# ArduinoZero.net
KiCad netlist of a schematic drawn in EAGLE
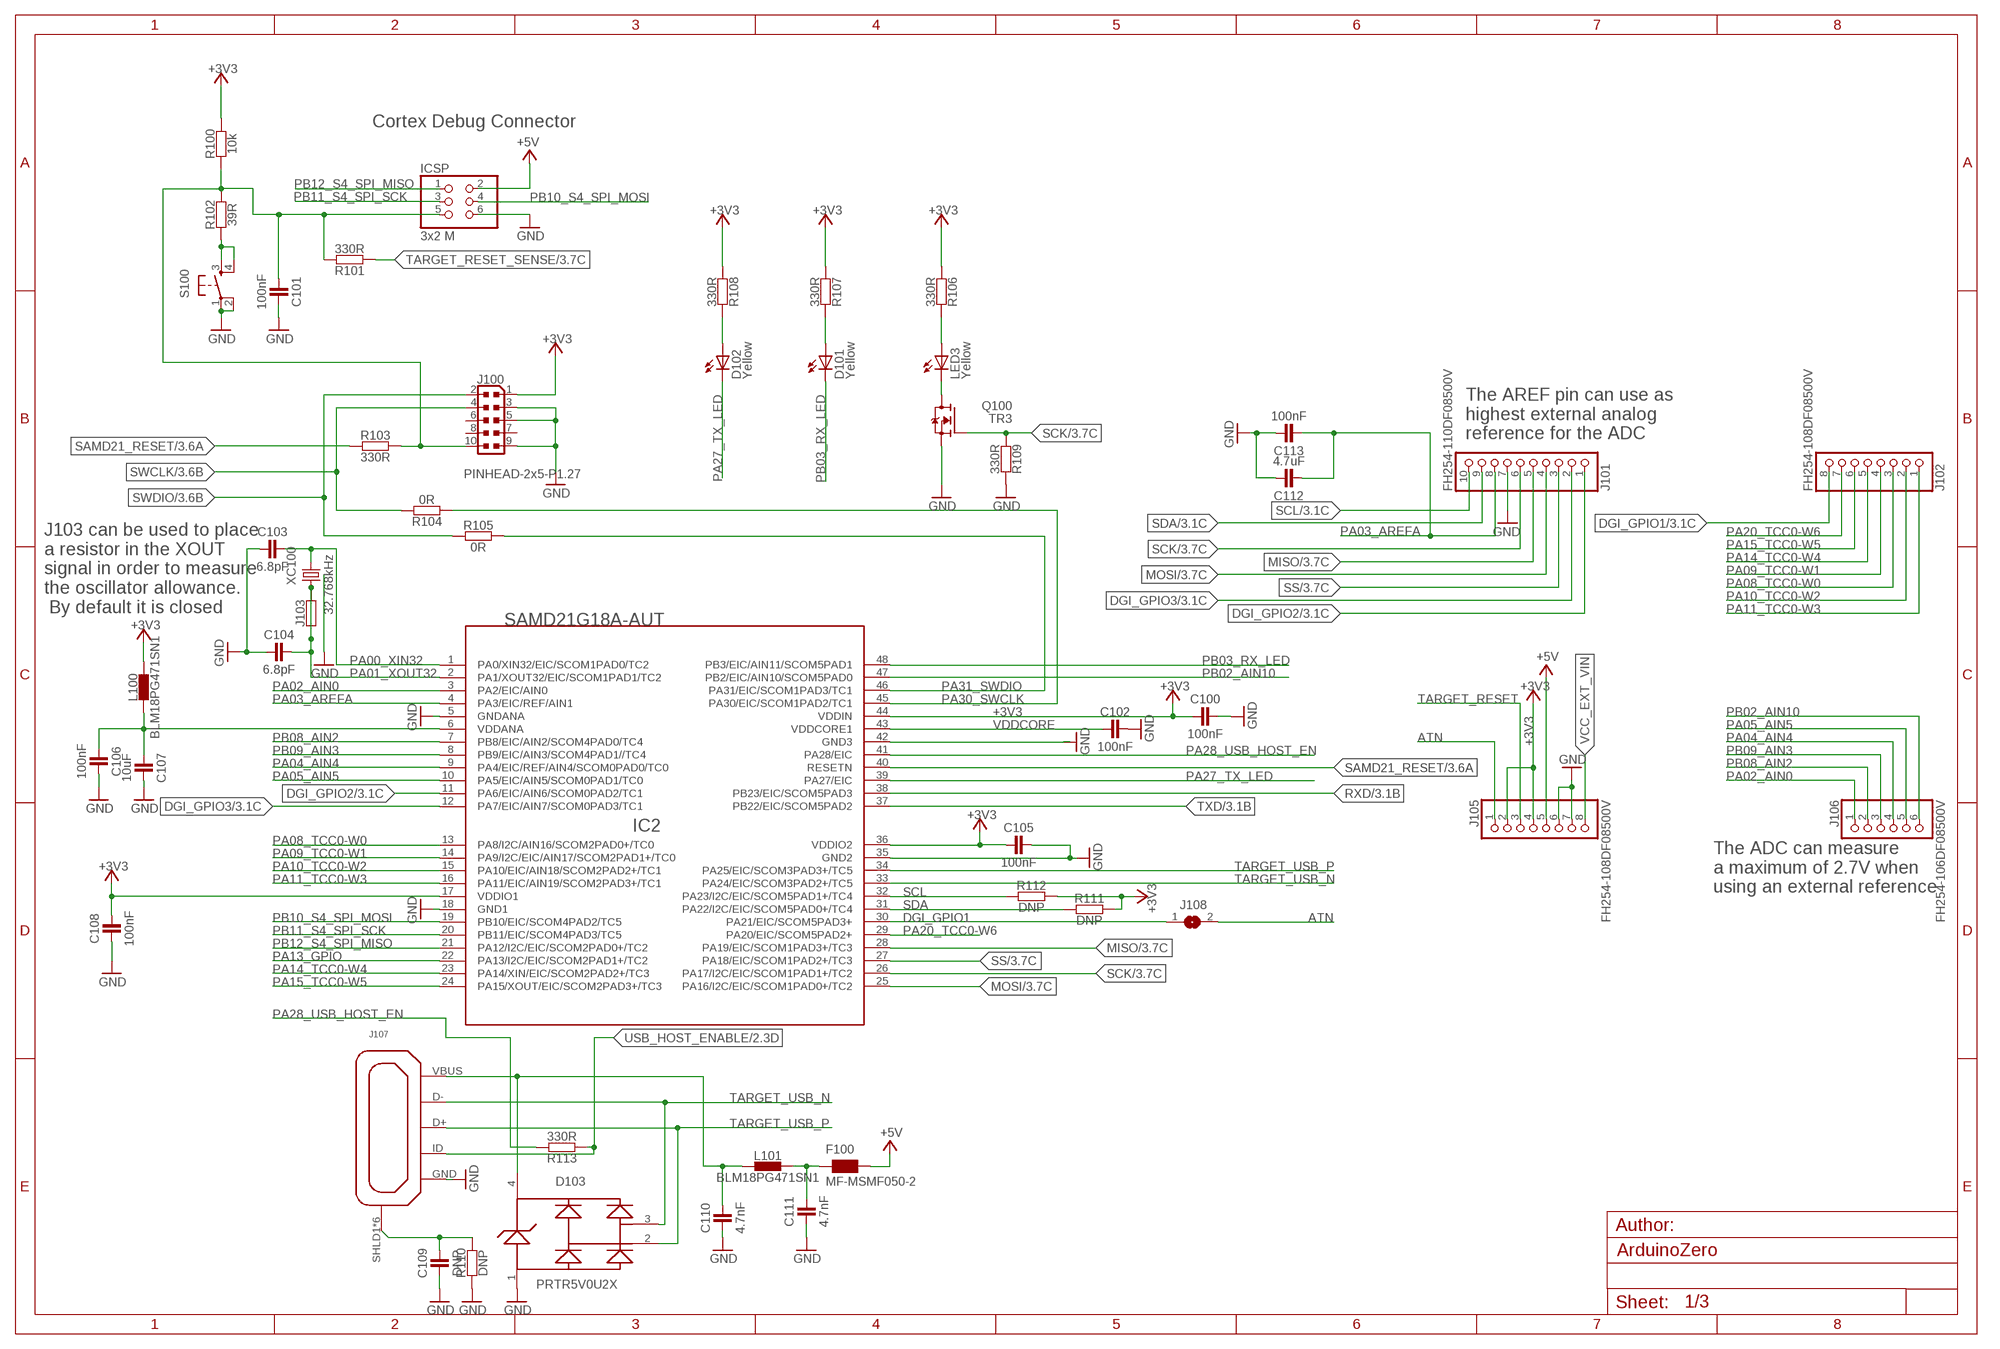
[diagram p0: schematic, sheet 1]
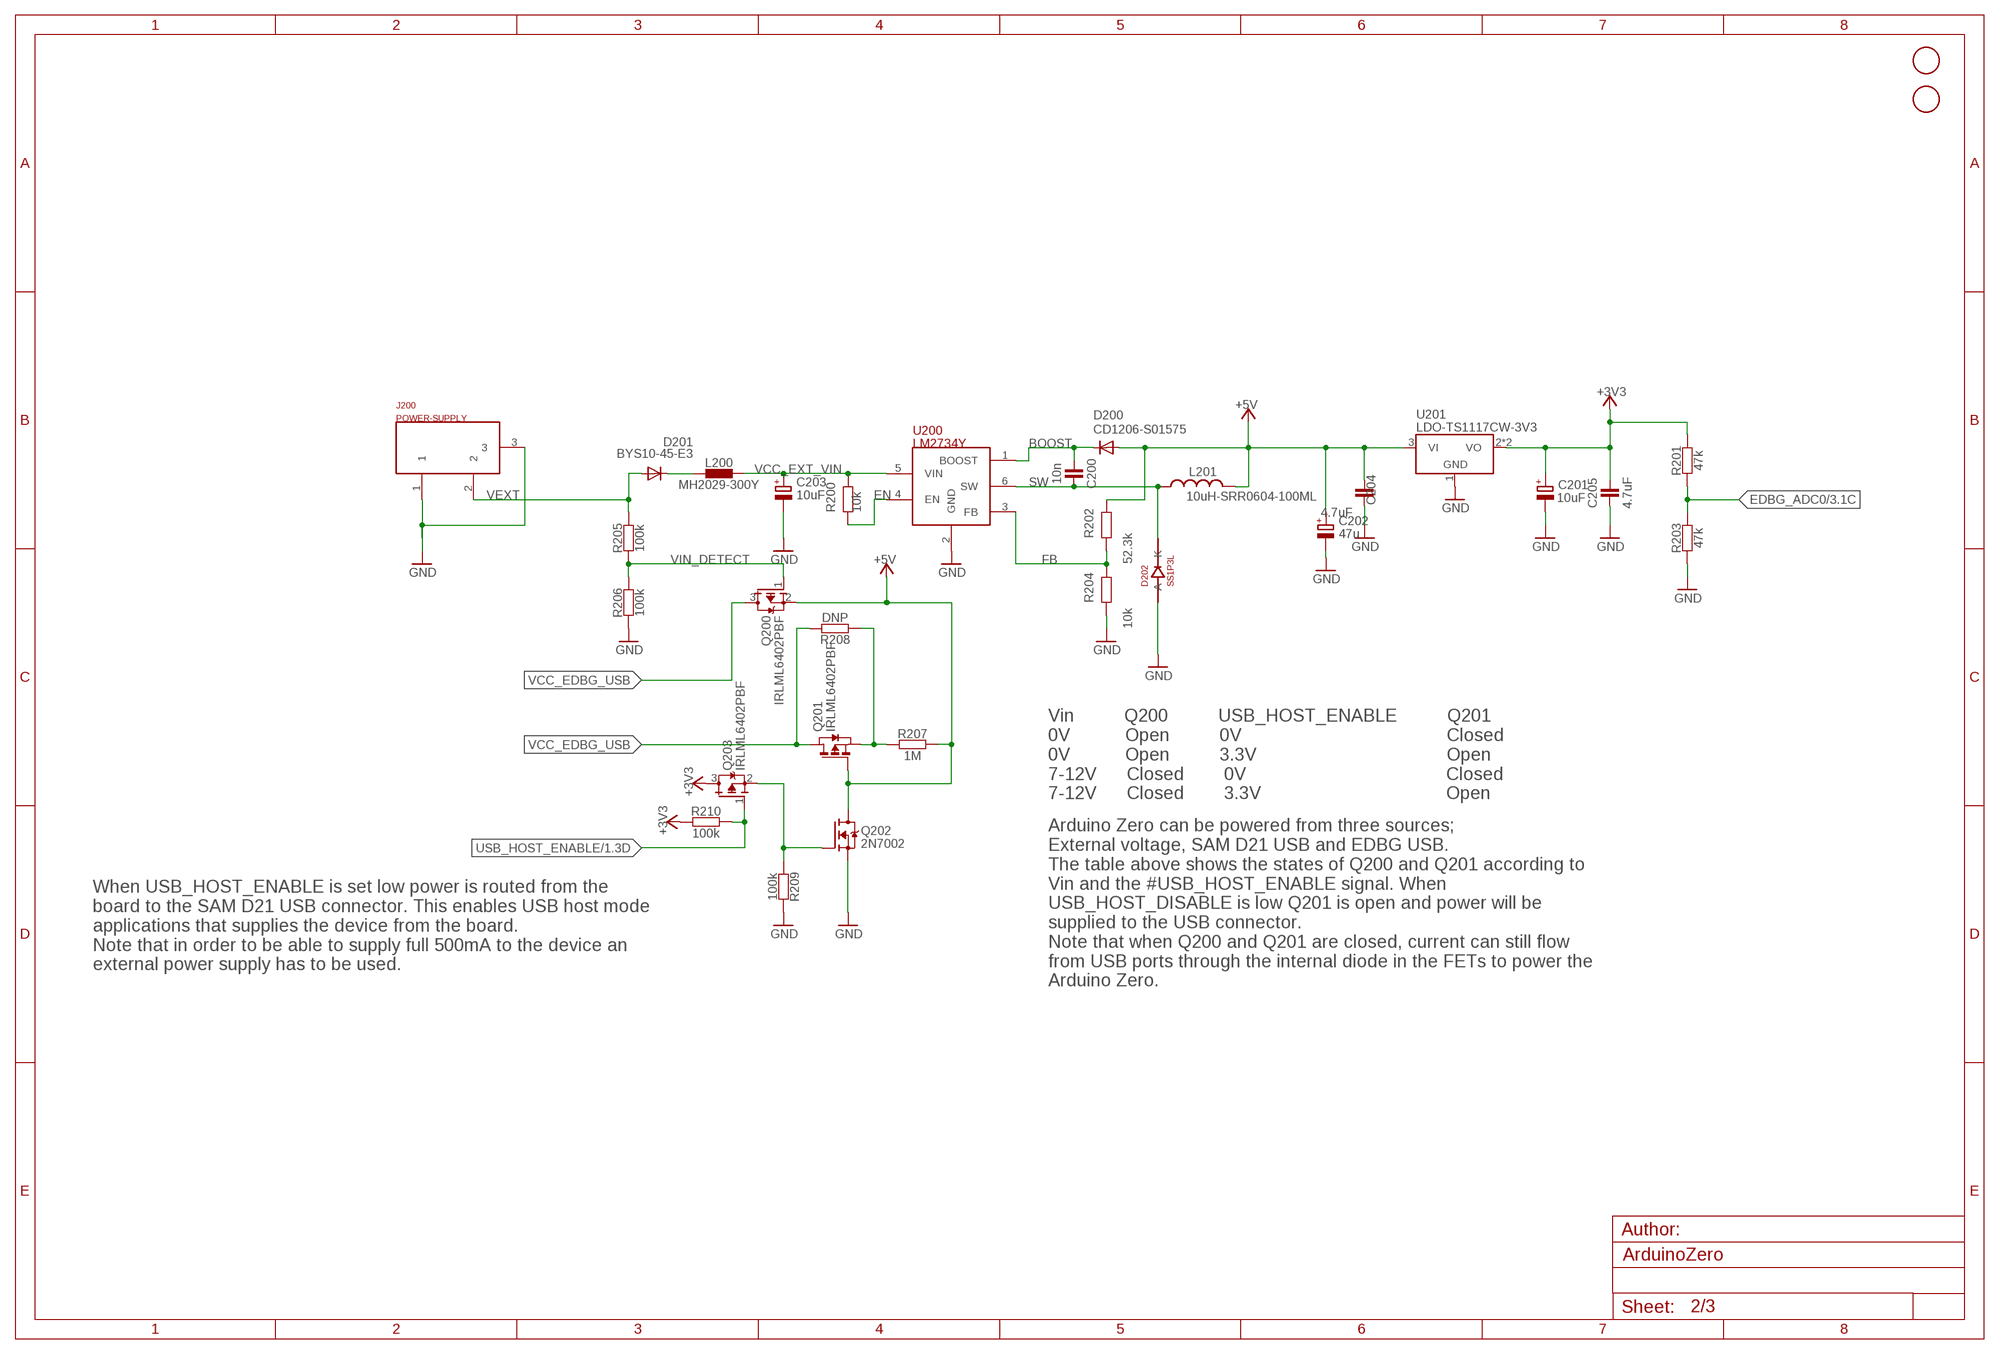
[diagram p1: schematic, sheet 2]
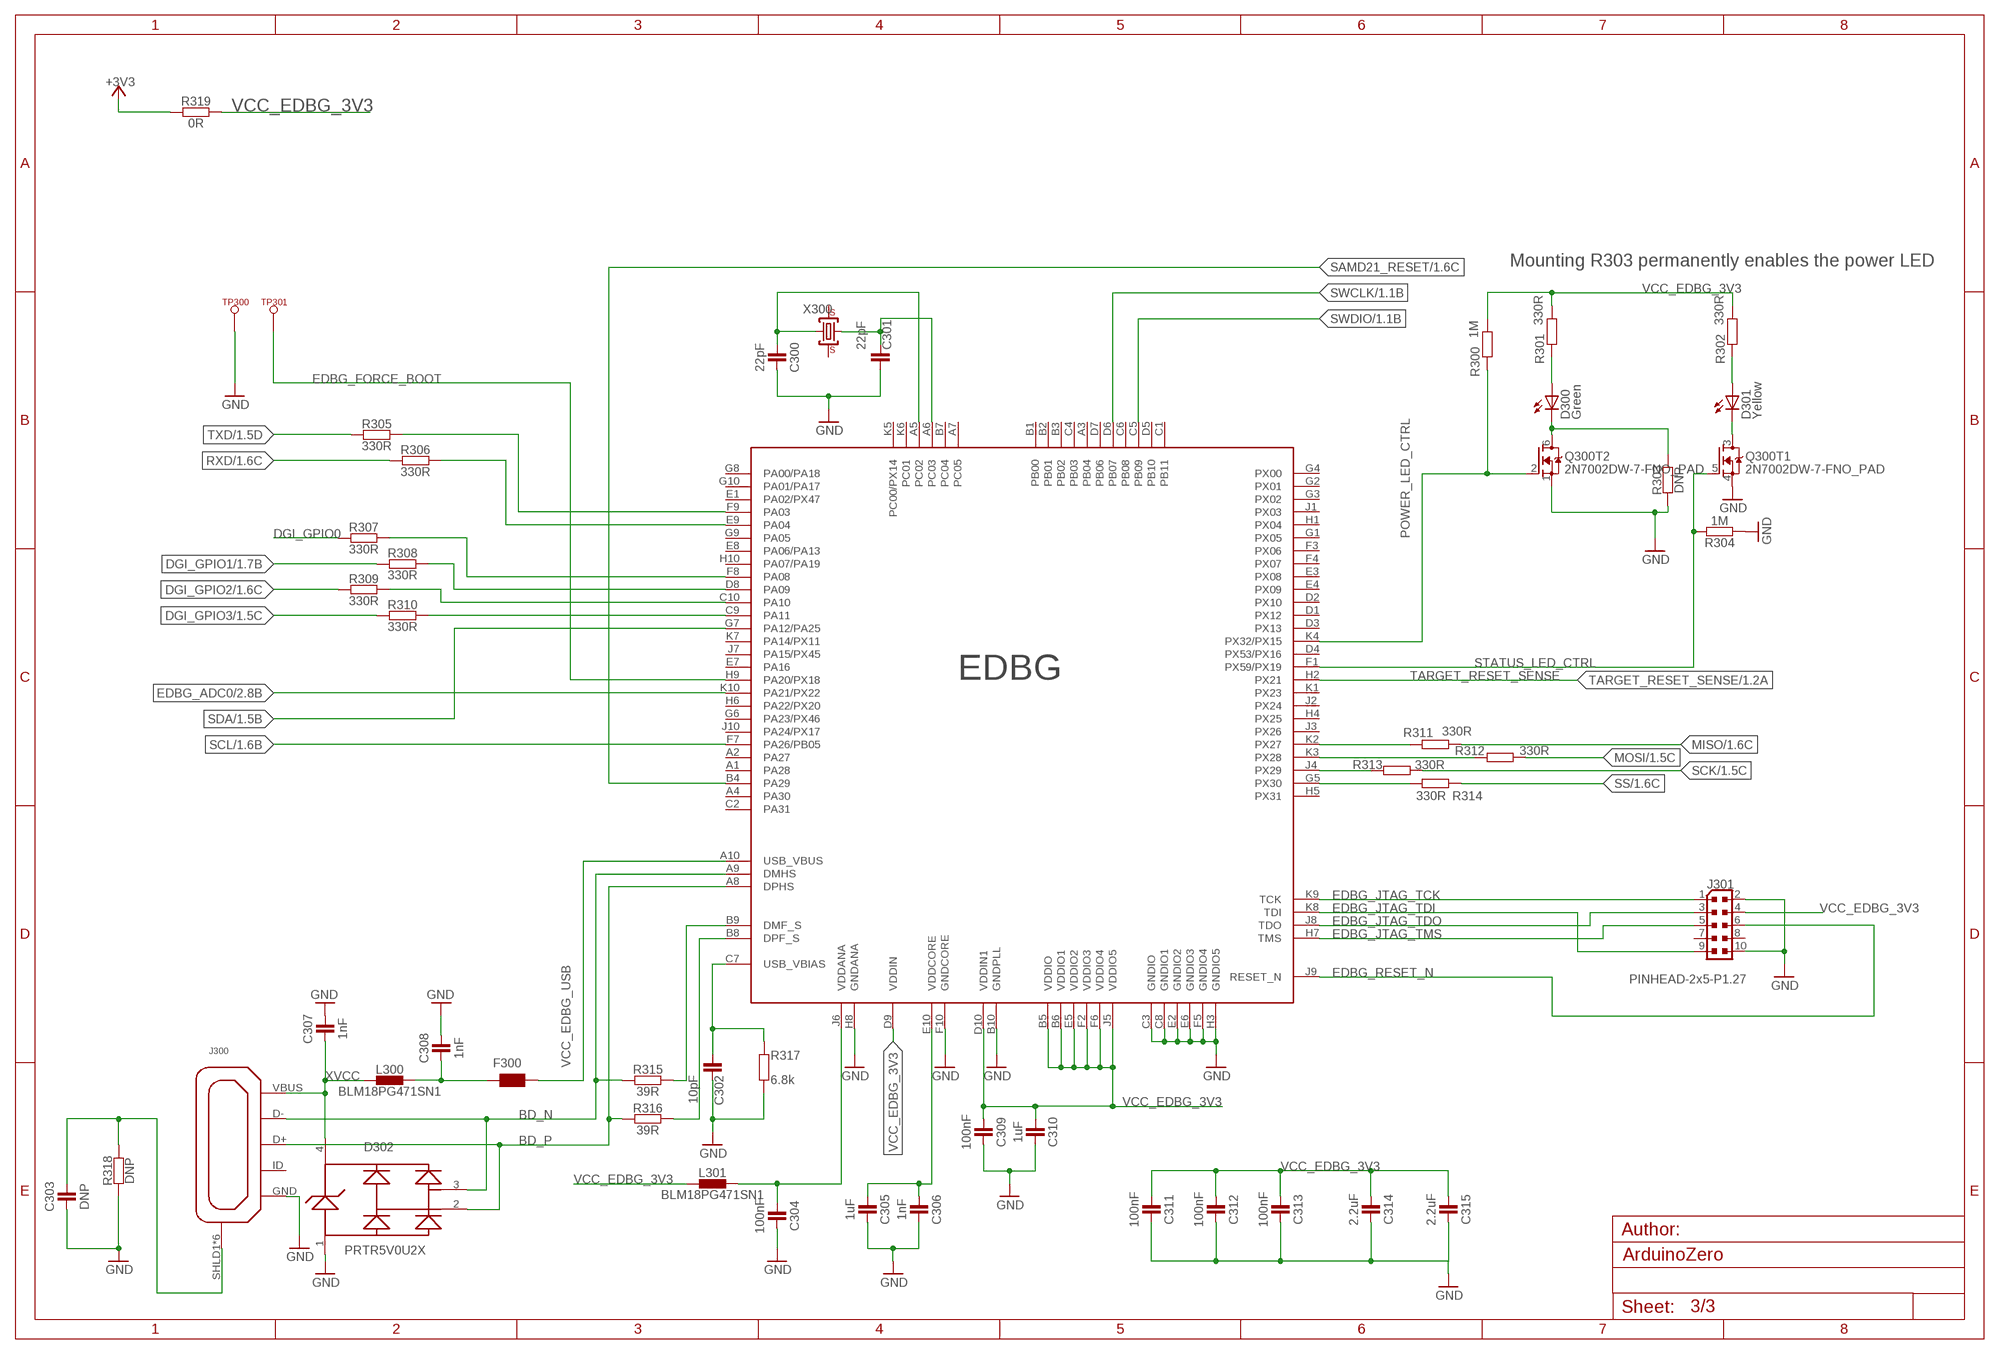
[diagram p2: schematic, sheet 3]

(export (version "E")
  (design (tool "Eeschema 10.0.6"))
  (components
    (comp (ref "C300")
      (value "22pF")
      (footprint "eagle-import:C0402")
      (libsource (lib "eagle-import") (part "CAPACITORS-0402"))
    )
    (comp (ref "C301")
      (value "22pF")
      (footprint "eagle-import:C0402")
      (libsource (lib "eagle-import") (part "CAPACITORS-0402"))
    )
    (comp (ref "C302")
      (value "10pF")
      (footprint "eagle-import:C0402")
      (libsource (lib "eagle-import") (part "CAPACITORS-0402"))
    )
    (comp (ref "C303")
      (value "DNP")
      (footprint "eagle-import:C0402")
      (libsource (lib "eagle-import") (part "CAPACITORS-0402"))
    )
    (comp (ref "C304")
      (value "100nF")
      (footprint "eagle-import:C0402")
      (libsource (lib "eagle-import") (part "CAPACITORS-0402"))
    )
    (comp (ref "C305")
      (value "1uF")
      (footprint "eagle-import:C0402")
      (libsource (lib "eagle-import") (part "CAPACITORS-0402"))
    )
    (comp (ref "C306")
      (value "1nF")
      (footprint "eagle-import:C0402")
      (libsource (lib "eagle-import") (part "CAPACITORS-0402"))
    )
    (comp (ref "C307")
      (value "1nF")
      (footprint "eagle-import:C0402")
      (libsource (lib "eagle-import") (part "CAPACITORS-0402"))
    )
    (comp (ref "C308")
      (value "1nF")
      (footprint "eagle-import:C0402")
      (libsource (lib "eagle-import") (part "CAPACITORS-0402"))
    )
    (comp (ref "C309")
      (value "100nF")
      (footprint "eagle-import:C0402")
      (libsource (lib "eagle-import") (part "CAPACITORS-0402"))
    )
    (comp (ref "C310")
      (value "1uF")
      (footprint "eagle-import:C0402")
      (libsource (lib "eagle-import") (part "CAPACITORS-0402"))
    )
    (comp (ref "C311")
      (value "100nF")
      (footprint "eagle-import:C0402")
      (libsource (lib "eagle-import") (part "CAPACITORS-0402"))
    )
    (comp (ref "C312")
      (value "100nF")
      (footprint "eagle-import:C0402")
      (libsource (lib "eagle-import") (part "CAPACITORS-0402"))
    )
    (comp (ref "C313")
      (value "100nF")
      (footprint "eagle-import:C0402")
      (libsource (lib "eagle-import") (part "CAPACITORS-0402"))
    )
    (comp (ref "C314")
      (value "2.2uF")
      (footprint "eagle-import:C0402")
      (libsource (lib "eagle-import") (part "CAPACITORS-0402"))
    )
    (comp (ref "C315")
      (value "2.2uF")
      (footprint "eagle-import:C0402")
      (libsource (lib "eagle-import") (part "CAPACITORS-0402"))
    )
    (comp (ref "D300")
      (value "Green")
      (footprint "eagle-import:CHIPLED_0805")
      (fields (field (name "PART_NUMBER") "KPT-2012SGC"))
      (libsource (lib "eagle-import") (part "0043_KPT-2012SGC"))
    )
    (comp (ref "D301")
      (value "Yellow")
      (footprint "eagle-import:CHIPLED_0805")
      (fields (field (name "PART_NUMBER") "KPT-2012SGC"))
      (libsource (lib "eagle-import") (part "0043_KPT-2012SGC"))
    )
    (comp (ref "D302")
      (value "PRTR5V0U2XB")
      (footprint "eagle-import:SOT143B")
      (libsource (lib "eagle-import") (part "PRTR5V0U2XB"))
    )
    (comp (ref "EDBG")
      (value "EDBG")
      (footprint "eagle-import:VFBGA100")
      (libsource (lib "eagle-import") (part "EDBG"))
    )
    (comp (ref "F300")
      (value "WUERTH-ELEKTRONIK_WE-CBF_1812")
      (footprint "eagle-import:WUERTH-ELEKTRONIK_1812")
      (libsource (lib "eagle-import") (part "WUERTH-ELEKTRONIK_WE-CBF_1812"))
    )
    (comp (ref "J300")
      (value "ZX62-AB-5PA")
      (footprint "eagle-import:USB-MICRO-10103594")
      (libsource (lib "eagle-import") (part "ZX62-AB-5PA"))
    )
    (comp (ref "J301")
      (value "PINHEAD-2x5-P1.27")
      (footprint "eagle-import:PINHEAD_2X05_127")
      (libsource (lib "eagle-import") (part "0171_PH127-205DF055G00AROUND-PADS"))
    )
    (comp (ref "L300")
      (value "BLM18PG471SN1")
      (footprint "eagle-import:C0603")
      (libsource (lib "eagle-import") (part "INDUCTOR-0603"))
    )
    (comp (ref "L301")
      (value "BLM18PG471SN1")
      (footprint "eagle-import:C0603")
      (libsource (lib "eagle-import") (part "INDUCTOR-0603"))
    )
    (comp (ref "Q300")
      (value "2N7002DW-7-FNO_PAD")
      (footprint "eagle-import:PWR_SC70-6L2")
      (libsource (lib "eagle-import") (part "2N7002DW-7-FNO_PAD"))
    )
    (comp (ref "R300")
      (value "1M")
      (footprint "eagle-import:C0402")
      (libsource (lib "eagle-import") (part "RESISTORS-0402"))
    )
    (comp (ref "R301")
      (value "330R")
      (footprint "eagle-import:C0402")
      (libsource (lib "eagle-import") (part "RESISTORS-0402"))
    )
    (comp (ref "R302")
      (value "330R")
      (footprint "eagle-import:C0402")
      (libsource (lib "eagle-import") (part "RESISTORS-0402"))
    )
    (comp (ref "R303")
      (value "DNP")
      (footprint "eagle-import:C0402")
      (libsource (lib "eagle-import") (part "RESISTORS-0402"))
    )
    (comp (ref "R304")
      (value "1M")
      (footprint "eagle-import:C0402")
      (libsource (lib "eagle-import") (part "RESISTORS-0402"))
    )
    (comp (ref "R305")
      (value "330R")
      (footprint "eagle-import:C0402")
      (libsource (lib "eagle-import") (part "RESISTORS-0402"))
    )
    (comp (ref "R306")
      (value "330R")
      (footprint "eagle-import:C0402")
      (libsource (lib "eagle-import") (part "RESISTORS-0402"))
    )
    (comp (ref "R307")
      (value "330R")
      (footprint "eagle-import:C0402")
      (libsource (lib "eagle-import") (part "RESISTORS-0402"))
    )
    (comp (ref "R308")
      (value "330R")
      (footprint "eagle-import:C0402")
      (libsource (lib "eagle-import") (part "RESISTORS-0402"))
    )
    (comp (ref "R309")
      (value "330R")
      (footprint "eagle-import:C0402")
      (libsource (lib "eagle-import") (part "RESISTORS-0402"))
    )
    (comp (ref "R310")
      (value "330R")
      (footprint "eagle-import:C0402")
      (libsource (lib "eagle-import") (part "RESISTORS-0402"))
    )
    (comp (ref "R311")
      (value "330R")
      (footprint "eagle-import:C0402")
      (libsource (lib "eagle-import") (part "RESISTORS-0402"))
    )
    (comp (ref "R312")
      (value "330R")
      (footprint "eagle-import:C0402")
      (libsource (lib "eagle-import") (part "RESISTORS-0402"))
    )
    (comp (ref "R313")
      (value "330R")
      (footprint "eagle-import:C0402")
      (libsource (lib "eagle-import") (part "RESISTORS-0402"))
    )
    (comp (ref "R314")
      (value "330R")
      (footprint "eagle-import:C0402")
      (libsource (lib "eagle-import") (part "RESISTORS-0402"))
    )
    (comp (ref "R315")
      (value "39R")
      (footprint "eagle-import:C0402")
      (libsource (lib "eagle-import") (part "RESISTORS-0402"))
    )
    (comp (ref "R316")
      (value "39R")
      (footprint "eagle-import:C0402")
      (libsource (lib "eagle-import") (part "RESISTORS-0402"))
    )
    (comp (ref "R317")
      (value "6.8k")
      (footprint "eagle-import:C0402")
      (libsource (lib "eagle-import") (part "RESISTORS-0402"))
    )
    (comp (ref "R318")
      (value "DNP")
      (footprint "eagle-import:C0402")
      (libsource (lib "eagle-import") (part "RESISTORS-0402"))
    )
    (comp (ref "R319")
      (value "0R")
      (footprint "eagle-import:C0402")
      (libsource (lib "eagle-import") (part "RESISTORS-0402"))
    )
    (comp (ref "TP300")
      (value "TP_SP")
      (footprint "eagle-import:TP-SP")
      (libsource (lib "eagle-import") (part "TP_SP"))
    )
    (comp (ref "TP301")
      (value "TP_SP")
      (footprint "eagle-import:TP-SP")
      (libsource (lib "eagle-import") (part "TP_SP"))
    )
    (comp (ref "X300")
      (value "12mHz-12pF-K7")
      (footprint "eagle-import:CRYSTAL-5.4-3.2")
      (libsource (lib "eagle-import") (part "12MHZ-12PF-K75.4-3.2"))
    )
    (comp (ref "C200")
      (value "10n")
      (footprint "eagle-import:C0402")
      (libsource (lib "eagle-import") (part "CAPACITORS-0402"))
    )
    (comp (ref "C201")
      (value "10uF")
      (footprint "eagle-import:PANASONIC_D")
      (fields (field (name "PART_NUMBER") "47uF"))
      (libsource (lib "eagle-import") (part "0113_47UF"))
    )
    (comp (ref "C202")
      (value "47u")
      (footprint "eagle-import:PANASONIC_D")
      (fields (field (name "PART_NUMBER") "47uF"))
      (libsource (lib "eagle-import") (part "0113_47UF"))
    )
    (comp (ref "C203")
      (value "10uF")
      (footprint "eagle-import:PANASONIC_D")
      (fields (field (name "PART_NUMBER") "47uF"))
      (libsource (lib "eagle-import") (part "0113_47UF"))
    )
    (comp (ref "C204")
      (value "4.7uF")
      (footprint "eagle-import:C0603")
      (libsource (lib "eagle-import") (part "CAPACITORS-0603"))
    )
    (comp (ref "C205")
      (value "4.7uF")
      (footprint "eagle-import:C0603")
      (libsource (lib "eagle-import") (part "CAPACITORS-0603"))
    )
    (comp (ref "D200")
      (value "CD1206-S01575")
      (footprint "eagle-import:MINIMELF")
      (libsource (lib "eagle-import") (part "0012_CD1206-S01575"))
    )
    (comp (ref "D201")
      (value "BYS10-45-E3")
      (footprint "eagle-import:MINIMELF")
      (fields (field (name "PART_NUMBER") "CD1206-S01575"))
      (libsource (lib "eagle-import") (part "0012_CD1206-S01575"))
    )
    (comp (ref "D202")
      (value "SS1P3L")
      (footprint "eagle-import:DO220AAL")
      (fields (field (name "PART_NUMBER") "SS1P3L-M3/84A"))
      (libsource (lib "eagle-import") (part "0025_SS1P3L-M3/84A"))
    )
    (comp (ref "FD1")
      (value "FIDUCIALMOUNT")
      (footprint "eagle-import:FIDUCIA-MOUNT")
      (libsource (lib "eagle-import") (part "FIDUCIALMOUNT"))
    )
    (comp (ref "FD2")
      (value "FIDUCIALMOUNT")
      (footprint "eagle-import:FIDUCIA-MOUNT")
      (libsource (lib "eagle-import") (part "FIDUCIALMOUNT"))
    )
    (comp (ref "J200")
      (value "POWER-SUPPLY")
      (footprint "eagle-import:POWERSUPPLY_DC-21MM")
      (fields (field (name "PART_NUMBER") "19746"))
      (libsource (lib "eagle-import") (part "0018_19746-POWER-SUPPLY"))
    )
    (comp (ref "L200")
      (value "MH2029-300Y")
      (footprint "eagle-import:C0805")
      (libsource (lib "eagle-import") (part "INDUCTOR-0805"))
    )
    (comp (ref "L201")
      (value "10uH-SRR0604-100ML")
      (footprint "eagle-import:SRR0604")
      (fields (field (name "PART_NUMBER") "SRR0604-100ML"))
      (libsource (lib "eagle-import") (part "0031_SRR0604-100ML"))
    )
    (comp (ref "Q200")
      (value "IRLML6402PBF")
      (footprint "eagle-import:SOT323")
      (libsource (lib "eagle-import") (part "IRLML6402PBF"))
    )
    (comp (ref "Q201")
      (value "IRLML6402PBF")
      (footprint "eagle-import:SOT-23")
      (fields (field (name "PART_NUMBER") "PMV48XP"))
      (libsource (lib "eagle-import") (part "0297_PMV48XP"))
    )
    (comp (ref "Q202")
      (value "2N7002")
      (footprint "eagle-import:SOT23")
      (libsource (lib "eagle-import") (part "MOSFET-N-SOT23"))
    )
    (comp (ref "Q203")
      (value "IRLML6402PBF")
      (footprint "eagle-import:SOT323")
      (libsource (lib "eagle-import") (part "IRLML6402PBF"))
    )
    (comp (ref "R200")
      (value "10k")
      (footprint "eagle-import:C0402")
      (libsource (lib "eagle-import") (part "RESISTORS-0402"))
    )
    (comp (ref "R201")
      (value "47k")
      (footprint "eagle-import:C0402")
      (libsource (lib "eagle-import") (part "RESISTORS-0402"))
    )
    (comp (ref "R202")
      (value "52.3k")
      (footprint "eagle-import:C0402")
      (libsource (lib "eagle-import") (part "RESISTORS-0402"))
    )
    (comp (ref "R203")
      (value "47k")
      (footprint "eagle-import:C0402")
      (libsource (lib "eagle-import") (part "RESISTORS-0402"))
    )
    (comp (ref "R204")
      (value "10k")
      (footprint "eagle-import:C0402")
      (libsource (lib "eagle-import") (part "RESISTORS-0402"))
    )
    (comp (ref "R205")
      (value "100k")
      (footprint "eagle-import:C0402")
      (libsource (lib "eagle-import") (part "RESISTORS-0402"))
    )
    (comp (ref "R206")
      (value "100k")
      (footprint "eagle-import:C0402")
      (libsource (lib "eagle-import") (part "RESISTORS-0402"))
    )
    (comp (ref "R207")
      (value "1M")
      (footprint "eagle-import:C0402")
      (libsource (lib "eagle-import") (part "RESISTORS-0402"))
    )
    (comp (ref "R208")
      (value "DNP")
      (footprint "eagle-import:C0402")
      (libsource (lib "eagle-import") (part "RESISTORS-0402"))
    )
    (comp (ref "R209")
      (value "100k")
      (footprint "eagle-import:C0402")
      (libsource (lib "eagle-import") (part "RESISTORS-0402"))
    )
    (comp (ref "R210")
      (value "100k")
      (footprint "eagle-import:C0402")
      (libsource (lib "eagle-import") (part "RESISTORS-0402"))
    )
    (comp (ref "U200")
      (value "LM2734Y")
      (footprint "eagle-import:SOT23-6")
      (fields (field (name "PART_NUMBER") "LM2734YMK"))
      (libsource (lib "eagle-import") (part "0179_LM2734YMK"))
    )
    (comp (ref "U201")
      (value "LDO-TS1117CW-3V3")
      (footprint "eagle-import:SOT223")
      (libsource (lib "eagle-import") (part "LDO-TS1117CW-3V3"))
    )
    (comp (ref "C100")
      (value "100nF")
      (footprint "eagle-import:C0402")
      (libsource (lib "eagle-import") (part "CAPACITORS-0402"))
    )
    (comp (ref "C101")
      (value "100nF")
      (footprint "eagle-import:C0402")
      (libsource (lib "eagle-import") (part "CAPACITORS-0402"))
    )
    (comp (ref "C102")
      (value "100nF")
      (footprint "eagle-import:C0402")
      (libsource (lib "eagle-import") (part "CAPACITORS-0402"))
    )
    (comp (ref "C103")
      (value "6.8pF")
      (footprint "eagle-import:C0402")
      (libsource (lib "eagle-import") (part "CAPACITORS-0402"))
    )
    (comp (ref "C104")
      (value "6.8pF")
      (footprint "eagle-import:C0402")
      (libsource (lib "eagle-import") (part "CAPACITORS-0402"))
    )
    (comp (ref "C105")
      (value "100nF")
      (footprint "eagle-import:C0402")
      (libsource (lib "eagle-import") (part "CAPACITORS-0402"))
    )
    (comp (ref "C106")
      (value "100nF")
      (footprint "eagle-import:C0402")
      (libsource (lib "eagle-import") (part "CAPACITORS-0402"))
    )
    (comp (ref "C107")
      (value "10uF")
      (footprint "eagle-import:C0603")
      (libsource (lib "eagle-import") (part "CAPACITORS-0603"))
    )
    (comp (ref "C108")
      (value "100nF")
      (footprint "eagle-import:C0402")
      (libsource (lib "eagle-import") (part "CAPACITORS-0402"))
    )
    (comp (ref "C109")
      (value "DNP")
      (footprint "eagle-import:C0402")
      (libsource (lib "eagle-import") (part "CAPACITORS-0402"))
    )
    (comp (ref "C110")
      (value "4.7nF")
      (footprint "eagle-import:C0402")
      (libsource (lib "eagle-import") (part "CAPACITORS-0402"))
    )
    (comp (ref "C111")
      (value "4.7nF")
      (footprint "eagle-import:C0402")
      (libsource (lib "eagle-import") (part "CAPACITORS-0402"))
    )
    (comp (ref "C112")
      (value "4.7uF")
      (footprint "eagle-import:C0603")
      (libsource (lib "eagle-import") (part "CAPACITORS-0603"))
    )
    (comp (ref "C113")
      (value "100nF")
      (footprint "eagle-import:C0402")
      (libsource (lib "eagle-import") (part "CAPACITORS-0402"))
    )
    (comp (ref "D101")
      (value "Yellow")
      (footprint "eagle-import:CHIPLED_0805")
      (fields (field (name "PART_NUMBER") "KPT-2012YC"))
      (libsource (lib "eagle-import") (part "0044_KPT-2012YC"))
    )
    (comp (ref "D102")
      (value "Yellow")
      (footprint "eagle-import:CHIPLED_0805")
      (fields (field (name "PART_NUMBER") "KPT-2012YC"))
      (libsource (lib "eagle-import") (part "0044_KPT-2012YC"))
    )
    (comp (ref "D103")
      (value "PRTR5V0U2XB")
      (footprint "eagle-import:SOT143B")
      (libsource (lib "eagle-import") (part "PRTR5V0U2XB"))
    )
    (comp (ref "F100")
      (value "MF-MSMF050-2")
      (footprint "eagle-import:WUERTH-ELEKTRONIK_1812")
      (libsource (lib "eagle-import") (part "WUERTH-ELEKTRONIK_WE-CBF_1812"))
    )
    (comp (ref "IC2")
      (value "SAMD21G18A-AUT")
      (footprint "eagle-import:TQFP48")
      (libsource (lib "eagle-import") (part "SAMD21G18A"))
    )
    (comp (ref "ICSP")
      (value "3x2 M")
      (footprint "eagle-import:2X03")
      (libsource (lib "eagle-import") (part "ICSP"))
    )
    (comp (ref "J100")
      (value "PINHEAD-2x5-P1.27")
      (footprint "eagle-import:PINHEAD_2X05_127")
      (libsource (lib "eagle-import") (part "0171_PH127-205DF055G00AROUND-PADS"))
    )
    (comp (ref "J101")
      (value "FH254-110DF08500V")
      (footprint "eagle-import:1X10")
      (fields (field (name "PART_NUMBER") "20TW-537"))
      (libsource (lib "eagle-import") (part "1684_20TW-537"))
    )
    (comp (ref "J102")
      (value "FH254-108DF08500V")
      (footprint "eagle-import:1X08")
      (fields (field (name "PART_NUMBER") "20TW-536"))
      (libsource (lib "eagle-import") (part "1683_20TW-536"))
    )
    (comp (ref "J103")
      (value "RESISTORS-0402")
      (footprint "eagle-import:C0402")
      (libsource (lib "eagle-import") (part "RESISTORS-0402"))
    )
    (comp (ref "J105")
      (value "FH254-108DF08500V")
      (footprint "eagle-import:1X08")
      (fields (field (name "PART_NUMBER") "20TW-536"))
      (libsource (lib "eagle-import") (part "1683_20TW-536"))
    )
    (comp (ref "J106")
      (value "FH254-106DF08500V")
      (footprint "eagle-import:1X06")
      (fields (field (name "PART_NUMBER") "20TW-535"))
      (libsource (lib "eagle-import") (part "1682_20TW-535_STD"))
    )
    (comp (ref "J107")
      (value "ZX62-AB-5PA")
      (footprint "eagle-import:USB-MICRO-10103594")
      (libsource (lib "eagle-import") (part "ZX62-AB-5PA"))
    )
    (comp (ref "J108")
      (value "SJ")
      (footprint "eagle-import:SJ")
      (libsource (lib "eagle-import") (part "SJ"))
    )
    (comp (ref "L100")
      (value "BLM18PG471SN1")
      (footprint "eagle-import:C0603")
      (libsource (lib "eagle-import") (part "INDUCTOR-0603"))
    )
    (comp (ref "L101")
      (value "BLM18PG471SN1")
      (footprint "eagle-import:C0603")
      (libsource (lib "eagle-import") (part "INDUCTOR-0603"))
    )
    (comp (ref "LED3")
      (value "Yellow")
      (footprint "eagle-import:CHIPLED_0805")
      (fields (field (name "PART_NUMBER") "KPT-2012YC"))
      (libsource (lib "eagle-import") (part "0044_KPT-2012YC"))
    )
    (comp (ref "R100")
      (value "10k")
      (footprint "eagle-import:C0402")
      (libsource (lib "eagle-import") (part "RESISTORS-0402"))
    )
    (comp (ref "R101")
      (value "330R")
      (footprint "eagle-import:C0402")
      (libsource (lib "eagle-import") (part "RESISTORS-0402"))
    )
    (comp (ref "R102")
      (value "39R")
      (footprint "eagle-import:C0402")
      (libsource (lib "eagle-import") (part "RESISTORS-0402"))
    )
    (comp (ref "R103")
      (value "330R")
      (footprint "eagle-import:C0402")
      (libsource (lib "eagle-import") (part "RESISTORS-0402"))
    )
    (comp (ref "R104")
      (value "0R")
      (footprint "eagle-import:C0402")
      (libsource (lib "eagle-import") (part "RESISTORS-0402"))
    )
    (comp (ref "R105")
      (value "0R")
      (footprint "eagle-import:C0402")
      (libsource (lib "eagle-import") (part "RESISTORS-0402"))
    )
    (comp (ref "R106")
      (value "330R")
      (footprint "eagle-import:C0402")
      (libsource (lib "eagle-import") (part "RESISTORS-0402"))
    )
    (comp (ref "R107")
      (value "330R")
      (footprint "eagle-import:C0402")
      (libsource (lib "eagle-import") (part "RESISTORS-0402"))
    )
    (comp (ref "R108")
      (value "330R")
      (footprint "eagle-import:C0402")
      (libsource (lib "eagle-import") (part "RESISTORS-0402"))
    )
    (comp (ref "R109")
      (value "330R")
      (footprint "eagle-import:C0402")
      (libsource (lib "eagle-import") (part "RESISTORS-0402"))
    )
    (comp (ref "R110")
      (value "DNP")
      (footprint "eagle-import:C0402")
      (libsource (lib "eagle-import") (part "RESISTORS-0402"))
    )
    (comp (ref "R111")
      (value "DNP")
      (footprint "eagle-import:C0402")
      (libsource (lib "eagle-import") (part "RESISTORS-0402"))
    )
    (comp (ref "R112")
      (value "DNP")
      (footprint "eagle-import:C0402")
      (libsource (lib "eagle-import") (part "RESISTORS-0402"))
    )
    (comp (ref "R113")
      (value "330R")
      (footprint "eagle-import:C0402")
      (libsource (lib "eagle-import") (part "RESISTORS-0402"))
    )
    (comp (ref "S100")
      (value "PUSHBUTTON3")
      (footprint "eagle-import:TS42_4PINS")
      (libsource (lib "eagle-import") (part "PUSHBUTTON3"))
    )
    (comp (ref "TR3")
      (value "Q100")
      (footprint "eagle-import:SOT-23")
      (libsource (lib "eagle-import") (part "1612_2N7002LT1G"))
    )
    (comp (ref "XC100")
      (value "32.768kHz")
      (footprint "eagle-import:CRYSTAL_TC26SMD")
      (libsource (lib "eagle-import") (part "CRYSTALSMD"))
    )
  )
  (nets
    (net (code "1") (name "+3V3") (class "Default")
      (node (ref "C100") (pin "1") (pinfunction "1_1") (pintype "passive"))
      (node (ref "C105") (pin "1") (pinfunction "1_1") (pintype "passive"))
      (node (ref "C108") (pin "2") (pinfunction "2_2") (pintype "passive"))
      (node (ref "C201") (pin "+") (pinfunction "+_+") (pintype "passive"))
      (node (ref "C205") (pin "2") (pinfunction "2_2") (pintype "passive"))
      (node (ref "IC2") (pin "17") (pinfunction "VDDIO1_17") (pintype "power_in"))
      (node (ref "IC2") (pin "36") (pinfunction "VDDIO2_36") (pintype "power_in"))
      (node (ref "IC2") (pin "44") (pinfunction "VDDIN_44") (pintype "power_in"))
      (node (ref "J100") (pin "1") (pinfunction "1_1") (pintype "passive"))
      (node (ref "J105") (pin "2") (pinfunction "2_2") (pintype "passive"))
      (node (ref "J105") (pin "4") (pinfunction "4_4") (pintype "passive"))
      (node (ref "L100") (pin "2") (pinfunction "2_2") (pintype "passive"))
      (node (ref "Q203") (pin "3") (pinfunction "D_3") (pintype "passive"))
      (node (ref "R100") (pin "2") (pinfunction "2_2") (pintype "passive"))
      (node (ref "R106") (pin "1") (pinfunction "1_1") (pintype "passive"))
      (node (ref "R107") (pin "1") (pinfunction "1_1") (pintype "passive"))
      (node (ref "R108") (pin "1") (pinfunction "1_1") (pintype "passive"))
      (node (ref "R111") (pin "2") (pinfunction "2_2") (pintype "passive"))
      (node (ref "R112") (pin "2") (pinfunction "2_2") (pintype "passive"))
      (node (ref "R201") (pin "2") (pinfunction "2_2") (pintype "passive"))
      (node (ref "R210") (pin "1") (pinfunction "1_1") (pintype "passive"))
      (node (ref "R319") (pin "1") (pinfunction "1_1") (pintype "passive"))
      (node (ref "U201") (pin "2") (pinfunction "VO_2") (pintype "passive"))
      (node (ref "U201") (pin "4") (pinfunction "VO_4") (pintype "passive"))
    )
    (net (code "2") (name "+5V") (class "Default")
      (node (ref "C202") (pin "+") (pinfunction "+_+") (pintype "passive"))
      (node (ref "C204") (pin "1") (pinfunction "1_1") (pintype "passive"))
      (node (ref "D200") (pin "A") (pinfunction "A_A") (pintype "passive"))
      (node (ref "F100") (pin "2") (pinfunction "2_2") (pintype "passive"))
      (node (ref "ICSP") (pin "2") (pinfunction "2_2") (pintype "passive"))
      (node (ref "J105") (pin "5") (pinfunction "5_5") (pintype "passive"))
      (node (ref "L201") (pin "P$2") (pinfunction "2_P$2") (pintype "passive"))
      (node (ref "Q200") (pin "2") (pinfunction "S_2") (pintype "passive"))
      (node (ref "Q201") (pin "3") (pinfunction "G_3") (pintype "passive"))
      (node (ref "Q202") (pin "3") (pinfunction "D_3") (pintype "passive"))
      (node (ref "R202") (pin "1") (pinfunction "1_1") (pintype "passive"))
      (node (ref "R207") (pin "2") (pinfunction "2_2") (pintype "passive"))
      (node (ref "U201") (pin "3") (pinfunction "VI_3") (pintype "input"))
    )
    (net (code "3") (name "ATN") (class "Default")
      (node (ref "J105") (pin "1") (pinfunction "1_1") (pintype "passive"))
      (node (ref "J108") (pin "2") (pinfunction "2_2") (pintype "passive"))
    )
    (net (code "4") (name "BD_N") (class "Default")
      (node (ref "D302") (pin "3") (pinfunction "3_3") (pintype "bidirectional"))
      (node (ref "EDBG") (pin "A9") (pinfunction "DMHS_A9") (pintype "bidirectional"))
      (node (ref "J300") (pin "D-") (pinfunction "D-_D-") (pintype "bidirectional"))
      (node (ref "R315") (pin "1") (pinfunction "1_1") (pintype "passive"))
    )
    (net (code "5") (name "BD_P") (class "Default")
      (node (ref "D302") (pin "2") (pinfunction "2_2") (pintype "bidirectional"))
      (node (ref "EDBG") (pin "A8") (pinfunction "DPHS_A8") (pintype "bidirectional"))
      (node (ref "J300") (pin "D+") (pinfunction "D+_D+") (pintype "bidirectional"))
      (node (ref "R316") (pin "1") (pinfunction "1_1") (pintype "passive"))
    )
    (net (code "6") (name "BOOST") (class "Default")
      (node (ref "C200") (pin "1") (pinfunction "1_1") (pintype "passive"))
      (node (ref "D200") (pin "C") (pinfunction "C_C") (pintype "passive"))
      (node (ref "U200") (pin "1") (pinfunction "BOOST_1") (pintype "input"))
    )
    (net (code "7") (name "DGI_GPIO0") (class "Default")
      (node (ref "R307") (pin "1") (pinfunction "1_1") (pintype "passive"))
    )
    (net (code "8") (name "DGI_GPIO1") (class "Default")
      (node (ref "IC2") (pin "30") (pinfunction "PA21/EIC/SCOM5PAD3+_30") (pintype "bidirectional"))
      (node (ref "J102") (pin "8") (pinfunction "8_8") (pintype "passive"))
      (node (ref "J108") (pin "1") (pinfunction "1_1") (pintype "passive"))
      (node (ref "R308") (pin "1") (pinfunction "1_1") (pintype "passive"))
    )
    (net (code "9") (name "DGI_GPIO2") (class "Default")
      (node (ref "IC2") (pin "11") (pinfunction "PA6/EIC/AIN6/SCOM0PAD2/TC1_11") (pintype "bidirectional"))
      (node (ref "J101") (pin "1") (pinfunction "1_1") (pintype "passive"))
      (node (ref "R309") (pin "1") (pinfunction "1_1") (pintype "passive"))
    )
    (net (code "10") (name "DGI_GPIO3") (class "Default")
      (node (ref "IC2") (pin "12") (pinfunction "PA7/EIC/AIN7/SCOM0PAD3/TC1_12") (pintype "bidirectional"))
      (node (ref "J101") (pin "2") (pinfunction "2_2") (pintype "passive"))
      (node (ref "R310") (pin "1") (pinfunction "1_1") (pintype "passive"))
    )
    (net (code "11") (name "EDBG_ADC0") (class "Default")
      (node (ref "EDBG") (pin "K10") (pinfunction "PA21/PX22_K10") (pintype "bidirectional"))
      (node (ref "R201") (pin "1") (pinfunction "1_1") (pintype "passive"))
      (node (ref "R203") (pin "2") (pinfunction "2_2") (pintype "passive"))
    )
    (net (code "12") (name "EDBG_FORCE_BOOT") (class "Default")
      (node (ref "EDBG") (pin "H9") (pinfunction "PA20/PX18_H9") (pintype "bidirectional"))
      (node (ref "TP301") (pin "X") (pinfunction "TESTP_X") (pintype "passive"))
    )
    (net (code "13") (name "EDBG_JTAG_TCK") (class "Default")
      (node (ref "EDBG") (pin "K9") (pinfunction "TCK_K9") (pintype "bidirectional"))
      (node (ref "J301") (pin "1") (pinfunction "1_1") (pintype "passive"))
    )
    (net (code "14") (name "EDBG_JTAG_TDI") (class "Default")
      (node (ref "EDBG") (pin "K8") (pinfunction "TDI_K8") (pintype "bidirectional"))
      (node (ref "J301") (pin "9") (pinfunction "9_9") (pintype "passive"))
    )
    (net (code "15") (name "EDBG_JTAG_TDO") (class "Default")
      (node (ref "EDBG") (pin "J8") (pinfunction "TDO_J8") (pintype "bidirectional"))
      (node (ref "J301") (pin "3") (pinfunction "3_3") (pintype "passive"))
    )
    (net (code "16") (name "EDBG_JTAG_TMS") (class "Default")
      (node (ref "EDBG") (pin "H7") (pinfunction "TMS_H7") (pintype "bidirectional"))
      (node (ref "J301") (pin "5") (pinfunction "5_5") (pintype "passive"))
    )
    (net (code "17") (name "EDBG_RESET_N") (class "Default")
      (node (ref "EDBG") (pin "J9") (pinfunction "RESET_N_J9") (pintype "bidirectional"))
      (node (ref "J301") (pin "6") (pinfunction "6_6") (pintype "passive"))
    )
    (net (code "18") (name "EN") (class "Default")
      (node (ref "R200") (pin "2") (pinfunction "2_2") (pintype "passive"))
      (node (ref "U200") (pin "4") (pinfunction "EN_4") (pintype "input"))
    )
    (net (code "19") (name "FB") (class "Default")
      (node (ref "R202") (pin "2") (pinfunction "2_2") (pintype "passive"))
      (node (ref "R204") (pin "1") (pinfunction "1_1") (pintype "passive"))
      (node (ref "U200") (pin "3") (pinfunction "FB_3") (pintype "input"))
    )
    (net (code "20") (name "GND") (class "Default")
      (node (ref "C100") (pin "2") (pinfunction "2_2") (pintype "passive"))
      (node (ref "C101") (pin "2") (pinfunction "2_2") (pintype "passive"))
      (node (ref "C102") (pin "2") (pinfunction "2_2") (pintype "passive"))
      (node (ref "C103") (pin "1") (pinfunction "1_1") (pintype "passive"))
      (node (ref "C104") (pin "1") (pinfunction "1_1") (pintype "passive"))
      (node (ref "C105") (pin "2") (pinfunction "2_2") (pintype "passive"))
      (node (ref "C106") (pin "2") (pinfunction "2_2") (pintype "passive"))
      (node (ref "C107") (pin "2") (pinfunction "2_2") (pintype "passive"))
      (node (ref "C108") (pin "1") (pinfunction "1_1") (pintype "passive"))
      (node (ref "C109") (pin "1") (pinfunction "1_1") (pintype "passive"))
      (node (ref "C110") (pin "1") (pinfunction "1_1") (pintype "passive"))
      (node (ref "C111") (pin "1") (pinfunction "1_1") (pintype "passive"))
      (node (ref "C112") (pin "2") (pinfunction "2_2") (pintype "passive"))
      (node (ref "C113") (pin "2") (pinfunction "2_2") (pintype "passive"))
      (node (ref "C201") (pin "-") (pinfunction "-_-") (pintype "passive"))
      (node (ref "C202") (pin "-") (pinfunction "-_-") (pintype "passive"))
      (node (ref "C203") (pin "-") (pinfunction "-_-") (pintype "passive"))
      (node (ref "C204") (pin "2") (pinfunction "2_2") (pintype "passive"))
      (node (ref "C205") (pin "1") (pinfunction "1_1") (pintype "passive"))
      (node (ref "C300") (pin "2") (pinfunction "2_2") (pintype "passive"))
      (node (ref "C301") (pin "2") (pinfunction "2_2") (pintype "passive"))
      (node (ref "C302") (pin "2") (pinfunction "2_2") (pintype "passive"))
      (node (ref "C303") (pin "1") (pinfunction "1_1") (pintype "passive"))
      (node (ref "C304") (pin "2") (pinfunction "2_2") (pintype "passive"))
      (node (ref "C305") (pin "2") (pinfunction "2_2") (pintype "passive"))
      (node (ref "C306") (pin "2") (pinfunction "2_2") (pintype "passive"))
      (node (ref "C307") (pin "2") (pinfunction "2_2") (pintype "passive"))
      (node (ref "C308") (pin "2") (pinfunction "2_2") (pintype "passive"))
      (node (ref "C309") (pin "2") (pinfunction "2_2") (pintype "passive"))
      (node (ref "C310") (pin "2") (pinfunction "2_2") (pintype "passive"))
      (node (ref "C311") (pin "2") (pinfunction "2_2") (pintype "passive"))
      (node (ref "C312") (pin "2") (pinfunction "2_2") (pintype "passive"))
      (node (ref "C313") (pin "2") (pinfunction "2_2") (pintype "passive"))
      (node (ref "C314") (pin "2") (pinfunction "2_2") (pintype "passive"))
      (node (ref "C315") (pin "2") (pinfunction "2_2") (pintype "passive"))
      (node (ref "D103") (pin "1") (pinfunction "1_1") (pintype "bidirectional"))
      (node (ref "D202") (pin "P$2") (pinfunction "A_P$2") (pintype "bidirectional"))
      (node (ref "D302") (pin "1") (pinfunction "1_1") (pintype "bidirectional"))
      (node (ref "EDBG") (pin "B10") (pinfunction "GNDPLL_B10") (pintype "bidirectional"))
      (node (ref "EDBG") (pin "C3") (pinfunction "GNDIO_C3") (pintype "bidirectional"))
      (node (ref "EDBG") (pin "C8") (pinfunction "GNDIO1_C8") (pintype "bidirectional"))
      (node (ref "EDBG") (pin "E2") (pinfunction "GNDIO2_E2") (pintype "bidirectional"))
      (node (ref "EDBG") (pin "E6") (pinfunction "GNDIO3_E6") (pintype "bidirectional"))
      (node (ref "EDBG") (pin "F10") (pinfunction "GNDCORE_F10") (pintype "bidirectional"))
      (node (ref "EDBG") (pin "F5") (pinfunction "GNDIO4_F5") (pintype "bidirectional"))
      (node (ref "EDBG") (pin "H3") (pinfunction "GNDIO5_H3") (pintype "bidirectional"))
      (node (ref "EDBG") (pin "H8") (pinfunction "GNDANA_H8") (pintype "bidirectional"))
      (node (ref "IC2") (pin "18") (pinfunction "GND1_18") (pintype "power_in"))
      (node (ref "IC2") (pin "35") (pinfunction "GND2_35") (pintype "power_in"))
      (node (ref "IC2") (pin "42") (pinfunction "GND3_42") (pintype "power_in"))
      (node (ref "IC2") (pin "5") (pinfunction "GNDANA_5") (pintype "power_in"))
      (node (ref "ICSP") (pin "6") (pinfunction "6_6") (pintype "passive"))
      (node (ref "J100") (pin "3") (pinfunction "3_3") (pintype "passive"))
      (node (ref "J100") (pin "5") (pinfunction "5_5") (pintype "passive"))
      (node (ref "J100") (pin "9") (pinfunction "9_9") (pintype "passive"))
      (node (ref "J101") (pin "7") (pinfunction "7_7") (pintype "passive"))
      (node (ref "J105") (pin "6") (pinfunction "6_6") (pintype "passive"))
      (node (ref "J105") (pin "7") (pinfunction "7_7") (pintype "passive"))
      (node (ref "J107") (pin "GND") (pinfunction "GND_GND") (pintype "bidirectional"))
      (node (ref "J200") (pin "1") (pinfunction "1_1") (pintype "power_in"))
      (node (ref "J200") (pin "3") (pinfunction "3_3") (pintype "power_in"))
      (node (ref "J300") (pin "GND") (pinfunction "GND_GND") (pintype "bidirectional"))
      (node (ref "J301") (pin "10") (pinfunction "10_10") (pintype "passive"))
      (node (ref "J301") (pin "2") (pinfunction "2_2") (pintype "passive"))
      (node (ref "Q202") (pin "2") (pinfunction "S_2") (pintype "passive"))
      (node (ref "Q300") (pin "1") (pinfunction "S_1") (pintype "passive"))
      (node (ref "Q300") (pin "4") (pinfunction "S_4") (pintype "passive"))
      (node (ref "R109") (pin "2") (pinfunction "2_2") (pintype "passive"))
      (node (ref "R110") (pin "1") (pinfunction "1_1") (pintype "passive"))
      (node (ref "R203") (pin "1") (pinfunction "1_1") (pintype "passive"))
      (node (ref "R204") (pin "2") (pinfunction "2_2") (pintype "passive"))
      (node (ref "R206") (pin "1") (pinfunction "1_1") (pintype "passive"))
      (node (ref "R209") (pin "2") (pinfunction "2_2") (pintype "passive"))
      (node (ref "R303") (pin "1") (pinfunction "1_1") (pintype "passive"))
      (node (ref "R304") (pin "1") (pinfunction "1_1") (pintype "passive"))
      (node (ref "R317") (pin "1") (pinfunction "1_1") (pintype "passive"))
      (node (ref "R318") (pin "1") (pinfunction "1_1") (pintype "passive"))
      (node (ref "S100") (pin "1") (pinfunction "1_1") (pintype "passive"))
      (node (ref "S100") (pin "2") (pinfunction "2_2") (pintype "passive"))
      (node (ref "TP300") (pin "X") (pinfunction "TESTP_X") (pintype "passive"))
      (node (ref "TR3") (pin "2") (pinfunction "S_2") (pintype "passive"))
      (node (ref "U200") (pin "2") (pinfunction "GND_2") (pintype "power_in"))
      (node (ref "U201") (pin "1") (pinfunction "GND_1") (pintype "passive"))
      (node (ref "XC100") (pin "P$1") (pinfunction "GND_P$1") (pintype "bidirectional"))
    )
    (net (code "21") (name "MISO") (class "Default")
      (node (ref "IC2") (pin "28") (pinfunction "PA19/EIC/SCOM1PAD3+/TC3_28") (pintype "bidirectional"))
      (node (ref "J101") (pin "5") (pinfunction "5_5") (pintype "passive"))
      (node (ref "R311") (pin "2") (pinfunction "2_2") (pintype "passive"))
    )
    (net (code "22") (name "MOSI") (class "Default")
      (node (ref "IC2") (pin "25") (pinfunction "PA16/I2C/EIC/SCOM1PAD0+/TC2_25") (pintype "bidirectional"))
      (node (ref "J101") (pin "4") (pinfunction "4_4") (pintype "passive"))
      (node (ref "R312") (pin "2") (pinfunction "2_2") (pintype "passive"))
    )
    (net (code "23") (name "Net-(C109-Pad2)") (class "Default")
      (node (ref "C109") (pin "2") (pinfunction "2_2") (pintype "passive"))
      (node (ref "J107") (pin "SHLD1") (pinfunction "SH_SHLD1") (pintype "bidirectional"))
      (node (ref "J107") (pin "SHLD2") (pinfunction "SH_SHLD2") (pintype "bidirectional"))
      (node (ref "J107") (pin "SHLD3") (pinfunction "SH_SHLD3") (pintype "bidirectional"))
      (node (ref "J107") (pin "SHLD4") (pinfunction "SH_SHLD4") (pintype "bidirectional"))
      (node (ref "J107") (pin "SHLD5") (pinfunction "SH_SHLD5") (pintype "bidirectional"))
      (node (ref "J107") (pin "SHLD6") (pinfunction "SH_SHLD6") (pintype "bidirectional"))
      (node (ref "R110") (pin "2") (pinfunction "2_2") (pintype "passive"))
    )
    (net (code "24") (name "Net-(C111-Pad2)") (class "Default")
      (node (ref "C111") (pin "2") (pinfunction "2_2") (pintype "passive"))
      (node (ref "F100") (pin "1") (pinfunction "1_1") (pintype "passive"))
      (node (ref "L101") (pin "2") (pinfunction "2_2") (pintype "passive"))
    )
    (net (code "25") (name "Net-(C303-Pad2)") (class "Default")
      (node (ref "C303") (pin "2") (pinfunction "2_2") (pintype "passive"))
      (node (ref "J300") (pin "SHLD1") (pinfunction "SH_SHLD1") (pintype "bidirectional"))
      (node (ref "J300") (pin "SHLD2") (pinfunction "SH_SHLD2") (pintype "bidirectional"))
      (node (ref "J300") (pin "SHLD3") (pinfunction "SH_SHLD3") (pintype "bidirectional"))
      (node (ref "J300") (pin "SHLD4") (pinfunction "SH_SHLD4") (pintype "bidirectional"))
      (node (ref "J300") (pin "SHLD5") (pinfunction "SH_SHLD5") (pintype "bidirectional"))
      (node (ref "J300") (pin "SHLD6") (pinfunction "SH_SHLD6") (pintype "bidirectional"))
      (node (ref "R318") (pin "2") (pinfunction "2_2") (pintype "passive"))
    )
    (net (code "26") (name "Net-(C308-Pad1)") (class "Default")
      (node (ref "C308") (pin "1") (pinfunction "1_1") (pintype "passive"))
      (node (ref "F300") (pin "1") (pinfunction "1_1") (pintype "passive"))
      (node (ref "L300") (pin "2") (pinfunction "2_2") (pintype "passive"))
    )
    (net (code "27") (name "Net-(D101-PadA)") (class "Default")
      (node (ref "D101") (pin "A") (pinfunction "A_A") (pintype "passive"))
      (node (ref "R107") (pin "2") (pinfunction "2_2") (pintype "passive"))
    )
    (net (code "28") (name "Net-(D102-PadA)") (class "Default")
      (node (ref "D102") (pin "A") (pinfunction "A_A") (pintype "passive"))
      (node (ref "R108") (pin "2") (pinfunction "2_2") (pintype "passive"))
    )
    (net (code "29") (name "Net-(D201-PadC)") (class "Default")
      (node (ref "D201") (pin "C") (pinfunction "C_C") (pintype "passive"))
      (node (ref "L200") (pin "1") (pinfunction "1_1") (pintype "passive"))
    )
    (net (code "30") (name "Net-(D300-PadA)") (class "Default")
      (node (ref "D300") (pin "A") (pinfunction "A_A") (pintype "passive"))
      (node (ref "R301") (pin "1") (pinfunction "1_1") (pintype "passive"))
    )
    (net (code "31") (name "Net-(D301-PadA)") (class "Default")
      (node (ref "D301") (pin "A") (pinfunction "A_A") (pintype "passive"))
      (node (ref "R302") (pin "1") (pinfunction "1_1") (pintype "passive"))
    )
    (net (code "32") (name "Net-(EDBG-DMF_S)") (class "Default")
      (node (ref "EDBG") (pin "B9") (pinfunction "DMF_S_B9") (pintype "bidirectional"))
      (node (ref "R315") (pin "2") (pinfunction "2_2") (pintype "passive"))
    )
    (net (code "33") (name "Net-(EDBG-DPF_S)") (class "Default")
      (node (ref "EDBG") (pin "B8") (pinfunction "DPF_S_B8") (pintype "bidirectional"))
      (node (ref "R316") (pin "2") (pinfunction "2_2") (pintype "passive"))
    )
    (net (code "34") (name "Net-(EDBG-PA03)") (class "Default")
      (node (ref "EDBG") (pin "F9") (pinfunction "PA03_F9") (pintype "bidirectional"))
      (node (ref "R305") (pin "2") (pinfunction "2_2") (pintype "passive"))
    )
    (net (code "35") (name "Net-(EDBG-PA04)") (class "Default")
      (node (ref "EDBG") (pin "E9") (pinfunction "PA04_E9") (pintype "bidirectional"))
      (node (ref "R306") (pin "2") (pinfunction "2_2") (pintype "passive"))
    )
    (net (code "36") (name "Net-(EDBG-PA08)") (class "Default")
      (node (ref "EDBG") (pin "F8") (pinfunction "PA08_F8") (pintype "bidirectional"))
      (node (ref "R307") (pin "2") (pinfunction "2_2") (pintype "passive"))
    )
    (net (code "37") (name "Net-(EDBG-PA09)") (class "Default")
      (node (ref "EDBG") (pin "D8") (pinfunction "PA09_D8") (pintype "bidirectional"))
      (node (ref "R308") (pin "2") (pinfunction "2_2") (pintype "passive"))
    )
    (net (code "38") (name "Net-(EDBG-PA10)") (class "Default")
      (node (ref "EDBG") (pin "C10") (pinfunction "PA10_C10") (pintype "bidirectional"))
      (node (ref "R309") (pin "2") (pinfunction "2_2") (pintype "passive"))
    )
    (net (code "39") (name "Net-(EDBG-PA11)") (class "Default")
      (node (ref "EDBG") (pin "C9") (pinfunction "PA11_C9") (pintype "bidirectional"))
      (node (ref "R310") (pin "2") (pinfunction "2_2") (pintype "passive"))
    )
    (net (code "40") (name "Net-(EDBG-PC02)") (class "Default")
      (node (ref "C300") (pin "1") (pinfunction "1_1") (pintype "passive"))
      (node (ref "EDBG") (pin "A5") (pinfunction "PC02_A5") (pintype "bidirectional"))
      (node (ref "X300") (pin "3") (pinfunction "C2_3") (pintype "passive"))
    )
    (net (code "41") (name "Net-(EDBG-PC03)") (class "Default")
      (node (ref "C301") (pin "1") (pinfunction "1_1") (pintype "passive"))
      (node (ref "EDBG") (pin "A6") (pinfunction "PC03_A6") (pintype "bidirectional"))
      (node (ref "X300") (pin "1") (pinfunction "C1_1") (pintype "passive"))
    )
    (net (code "42") (name "Net-(EDBG-PX27)") (class "Default")
      (node (ref "EDBG") (pin "K2") (pinfunction "PX27_K2") (pintype "bidirectional"))
      (node (ref "R311") (pin "1") (pinfunction "1_1") (pintype "passive"))
    )
    (net (code "43") (name "Net-(EDBG-PX28)") (class "Default")
      (node (ref "EDBG") (pin "K3") (pinfunction "PX28_K3") (pintype "bidirectional"))
      (node (ref "R312") (pin "1") (pinfunction "1_1") (pintype "passive"))
    )
    (net (code "44") (name "Net-(EDBG-PX29)") (class "Default")
      (node (ref "EDBG") (pin "J4") (pinfunction "PX29_J4") (pintype "bidirectional"))
      (node (ref "R313") (pin "1") (pinfunction "1_1") (pintype "passive"))
    )
    (net (code "45") (name "Net-(EDBG-PX30)") (class "Default")
      (node (ref "EDBG") (pin "G5") (pinfunction "PX30_G5") (pintype "bidirectional"))
      (node (ref "R314") (pin "1") (pinfunction "1_1") (pintype "passive"))
    )
    (net (code "46") (name "Net-(EDBG-USB_VBIAS)") (class "Default")
      (node (ref "C302") (pin "1") (pinfunction "1_1") (pintype "passive"))
      (node (ref "EDBG") (pin "C7") (pinfunction "USB_VBIAS_C7") (pintype "bidirectional"))
      (node (ref "R317") (pin "2") (pinfunction "2_2") (pintype "passive"))
    )
    (net (code "47") (name "Net-(EDBG-VDDANA)") (class "Default")
      (node (ref "C304") (pin "1") (pinfunction "1_1") (pintype "passive"))
      (node (ref "EDBG") (pin "J6") (pinfunction "VDDANA_J6") (pintype "bidirectional"))
      (node (ref "L301") (pin "2") (pinfunction "2_2") (pintype "passive"))
    )
    (net (code "48") (name "Net-(EDBG-VDDCORE)") (class "Default")
      (node (ref "C305") (pin "1") (pinfunction "1_1") (pintype "passive"))
      (node (ref "C306") (pin "1") (pinfunction "1_1") (pintype "passive"))
      (node (ref "EDBG") (pin "E10") (pinfunction "VDDCORE_E10") (pintype "bidirectional"))
    )
    (net (code "49") (name "Net-(IC2-VDDANA)") (class "Default")
      (node (ref "C106") (pin "1") (pinfunction "1_1") (pintype "passive"))
      (node (ref "C107") (pin "1") (pinfunction "1_1") (pintype "passive"))
      (node (ref "IC2") (pin "6") (pinfunction "VDDANA_6") (pintype "power_in"))
      (node (ref "L100") (pin "1") (pinfunction "1_1") (pintype "passive"))
    )
    (net (code "50") (name "Net-(J107-VUSB)") (class "Default")
      (node (ref "C110") (pin "2") (pinfunction "2_2") (pintype "passive"))
      (node (ref "D103") (pin "4") (pinfunction "4_4") (pintype "bidirectional"))
      (node (ref "J107") (pin "VBUS") (pinfunction "VUSB_VBUS") (pintype "bidirectional"))
      (node (ref "L101") (pin "1") (pinfunction "1_1") (pintype "passive"))
    )
    (net (code "51") (name "Net-(LED3-PadA)") (class "Default")
      (node (ref "LED3") (pin "A") (pinfunction "A_A") (pintype "passive"))
      (node (ref "R106") (pin "2") (pinfunction "2_2") (pintype "passive"))
    )
    (net (code "52") (name "Net-(Q201-S)") (class "Default")
      (node (ref "Q201") (pin "2") (pinfunction "S_2") (pintype "passive"))
      (node (ref "R207") (pin "1") (pinfunction "1_1") (pintype "passive"))
      (node (ref "R208") (pin "1") (pinfunction "1_1") (pintype "passive"))
    )
    (net (code "53") (name "Net-(Q202-G)") (class "Default")
      (node (ref "Q202") (pin "1") (pinfunction "G_1") (pintype "passive"))
      (node (ref "Q203") (pin "2") (pinfunction "S_2") (pintype "passive"))
      (node (ref "R209") (pin "1") (pinfunction "1_1") (pintype "passive"))
    )
    (net (code "54") (name "Net-(Q300A-D)") (class "Default")
      (node (ref "D301") (pin "C") (pinfunction "C_C") (pintype "passive"))
      (node (ref "Q300") (pin "3") (pinfunction "D_3") (pintype "passive"))
    )
    (net (code "55") (name "Net-(Q300B-D)") (class "Default")
      (node (ref "D300") (pin "C") (pinfunction "C_C") (pintype "passive"))
      (node (ref "Q300") (pin "6") (pinfunction "D_6") (pintype "passive"))
      (node (ref "R303") (pin "2") (pinfunction "2_2") (pintype "passive"))
    )
    (net (code "56") (name "Net-(R102-Pad1)") (class "Default")
      (node (ref "R102") (pin "1") (pinfunction "1_1") (pintype "passive"))
      (node (ref "S100") (pin "3") (pinfunction "3_3") (pintype "passive"))
      (node (ref "S100") (pin "4") (pinfunction "4_4") (pintype "passive"))
    )
    (net (code "57") (name "Net-(TR3-D)") (class "Default")
      (node (ref "LED3") (pin "C") (pinfunction "C_C") (pintype "passive"))
      (node (ref "TR3") (pin "1") (pinfunction "D_1") (pintype "passive"))
    )
    (net (code "58") (name "PA00_XIN32") (class "Default")
      (node (ref "C103") (pin "2") (pinfunction "2_2") (pintype "passive"))
      (node (ref "IC2") (pin "1") (pinfunction "PA0/XIN32/EIC/SCOM1PAD0/TC2_1") (pintype "bidirectional"))
      (node (ref "XC100") (pin "2") (pinfunction "2_2") (pintype "passive"))
    )
    (net (code "59") (name "PA01_XOUT32") (class "Default")
      (node (ref "C104") (pin "2") (pinfunction "2_2") (pintype "passive"))
      (node (ref "IC2") (pin "2") (pinfunction "PA1/XOUT32/EIC/SCOM1PAD1/TC2_2") (pintype "bidirectional"))
      (node (ref "J103") (pin "1") (pinfunction "1_1") (pintype "passive"))
      (node (ref "J103") (pin "2") (pinfunction "2_2") (pintype "passive"))
      (node (ref "XC100") (pin "1") (pinfunction "1_1") (pintype "passive"))
    )
    (net (code "60") (name "PA02_AIN0") (class "Default")
      (node (ref "IC2") (pin "3") (pinfunction "PA2/EIC/AIN0_3") (pintype "bidirectional"))
      (node (ref "J106") (pin "1") (pinfunction "1_1") (pintype "passive"))
    )
    (net (code "61") (name "PA03_AREFA") (class "Default")
      (node (ref "C112") (pin "1") (pinfunction "1_1") (pintype "passive"))
      (node (ref "C113") (pin "1") (pinfunction "1_1") (pintype "passive"))
      (node (ref "IC2") (pin "4") (pinfunction "PA3/EIC/REF/AIN1_4") (pintype "bidirectional"))
      (node (ref "J101") (pin "8") (pinfunction "8_8") (pintype "passive"))
    )
    (net (code "62") (name "PA04_AIN4") (class "Default")
      (node (ref "IC2") (pin "9") (pinfunction "PA4/EIC/REF/AIN4/SCOM0PAD0/TC0_9") (pintype "bidirectional"))
      (node (ref "J106") (pin "4") (pinfunction "4_4") (pintype "passive"))
    )
    (net (code "63") (name "PA05_AIN5") (class "Default")
      (node (ref "IC2") (pin "10") (pinfunction "PA5/EIC/AIN5/SCOM0PAD1/TC0_10") (pintype "bidirectional"))
      (node (ref "J106") (pin "5") (pinfunction "5_5") (pintype "passive"))
    )
    (net (code "64") (name "PA08_TCC0-W0") (class "Default")
      (node (ref "IC2") (pin "13") (pinfunction "PA8/I2C/AIN16/SCOM2PAD0+/TC0_13") (pintype "bidirectional"))
      (node (ref "J102") (pin "3") (pinfunction "3_3") (pintype "passive"))
    )
    (net (code "65") (name "PA09_TCC0-W1") (class "Default")
      (node (ref "IC2") (pin "14") (pinfunction "PA9/I2C/EIC/AIN17/SCOM2PAD1+/TC0_14") (pintype "bidirectional"))
      (node (ref "J102") (pin "4") (pinfunction "4_4") (pintype "passive"))
    )
    (net (code "66") (name "PA10_TCC0-W2") (class "Default")
      (node (ref "IC2") (pin "15") (pinfunction "PA10/EIC/AIN18/SCOM2PAD2+/TC1_15") (pintype "bidirectional"))
      (node (ref "J102") (pin "2") (pinfunction "2_2") (pintype "passive"))
    )
    (net (code "67") (name "PA11_TCC0-W3") (class "Default")
      (node (ref "IC2") (pin "16") (pinfunction "PA11/EIC/AIN19/SCOM2PAD3+/TC1_16") (pintype "bidirectional"))
      (node (ref "J102") (pin "1") (pinfunction "1_1") (pintype "passive"))
    )
    (net (code "68") (name "PA13_GPIO") (class "Default")
      (node (ref "IC2") (pin "22") (pinfunction "PA13/I2C/EIC/SCOM2PAD1+/TC2_22") (pintype "bidirectional"))
    )
    (net (code "69") (name "PA14_TCC0-W4") (class "Default")
      (node (ref "IC2") (pin "23") (pinfunction "PA14/XIN/EIC/SCOM2PAD2+/TC3_23") (pintype "bidirectional"))
      (node (ref "J102") (pin "5") (pinfunction "5_5") (pintype "passive"))
    )
    (net (code "70") (name "PA15_TCC0-W5") (class "Default")
      (node (ref "IC2") (pin "24") (pinfunction "PA15/XOUT/EIC/SCOM2PAD3+/TC3_24") (pintype "bidirectional"))
      (node (ref "J102") (pin "6") (pinfunction "6_6") (pintype "passive"))
    )
    (net (code "71") (name "PA20_TCC0-W6") (class "Default")
      (node (ref "IC2") (pin "29") (pinfunction "PA20/EIC/SCOM5PAD2+_29") (pintype "bidirectional"))
      (node (ref "J102") (pin "7") (pinfunction "7_7") (pintype "passive"))
    )
    (net (code "72") (name "PA27_TX_LED") (class "Default")
      (node (ref "D102") (pin "C") (pinfunction "C_C") (pintype "passive"))
      (node (ref "IC2") (pin "39") (pinfunction "PA27/EIC_39") (pintype "bidirectional"))
    )
    (net (code "73") (name "PA28_USB_HOST_EN") (class "Default")
      (node (ref "IC2") (pin "41") (pinfunction "PA28/EIC_41") (pintype "bidirectional"))
      (node (ref "R113") (pin "2") (pinfunction "2_2") (pintype "passive"))
    )
    (net (code "74") (name "PA30_SWCLK") (class "Default")
      (node (ref "IC2") (pin "45") (pinfunction "PA30/EIC/SCOM1PAD2/TC1_45") (pintype "bidirectional"))
      (node (ref "R104") (pin "1") (pinfunction "1_1") (pintype "passive"))
    )
    (net (code "75") (name "PA31_SWDIO") (class "Default")
      (node (ref "IC2") (pin "46") (pinfunction "PA31/EIC/SCOM1PAD3/TC1_46") (pintype "bidirectional"))
      (node (ref "R105") (pin "2") (pinfunction "2_2") (pintype "passive"))
    )
    (net (code "76") (name "PB02_AIN10") (class "Default")
      (node (ref "IC2") (pin "47") (pinfunction "PB2/EIC/AIN10/SCOM5PAD0_47") (pintype "bidirectional"))
      (node (ref "J106") (pin "6") (pinfunction "6_6") (pintype "passive"))
    )
    (net (code "77") (name "PB03_RX_LED") (class "Default")
      (node (ref "D101") (pin "C") (pinfunction "C_C") (pintype "passive"))
      (node (ref "IC2") (pin "48") (pinfunction "PB3/EIC/AIN11/SCOM5PAD1_48") (pintype "bidirectional"))
    )
    (net (code "78") (name "PB08_AIN2") (class "Default")
      (node (ref "IC2") (pin "7") (pinfunction "PB8/EIC/AIN2/SCOM4PAD0/TC4_7") (pintype "bidirectional"))
      (node (ref "J106") (pin "2") (pinfunction "2_2") (pintype "passive"))
    )
    (net (code "79") (name "PB09_AIN3") (class "Default")
      (node (ref "IC2") (pin "8") (pinfunction "PB9/EIC/AIN3/SCOM4PAD1//TC4_8") (pintype "bidirectional"))
      (node (ref "J106") (pin "3") (pinfunction "3_3") (pintype "passive"))
    )
    (net (code "80") (name "PB10_S4_SPI_MOSI") (class "Default")
      (node (ref "IC2") (pin "19") (pinfunction "PB10/EIC/SCOM4PAD2/TC5_19") (pintype "bidirectional"))
      (node (ref "ICSP") (pin "4") (pinfunction "4_4") (pintype "passive"))
    )
    (net (code "81") (name "PB11_S4_SPI_SCK") (class "Default")
      (node (ref "IC2") (pin "20") (pinfunction "PB11/EIC/SCOM4PAD3/TC5_20") (pintype "bidirectional"))
      (node (ref "ICSP") (pin "3") (pinfunction "3_3") (pintype "passive"))
    )
    (net (code "82") (name "PB12_S4_SPI_MISO") (class "Default")
      (node (ref "IC2") (pin "21") (pinfunction "PA12/I2C/EIC/SCOM2PAD0+/TC2_21") (pintype "bidirectional"))
      (node (ref "ICSP") (pin "1") (pinfunction "1_1") (pintype "passive"))
    )
    (net (code "83") (name "POWER_LED_CTRL") (class "Default")
      (node (ref "EDBG") (pin "K4") (pinfunction "PX32/PX15_K4") (pintype "bidirectional"))
      (node (ref "Q300") (pin "2") (pinfunction "G_2") (pintype "passive"))
      (node (ref "R300") (pin "1") (pinfunction "1_1") (pintype "passive"))
    )
    (net (code "84") (name "RXD") (class "Default")
      (node (ref "IC2") (pin "38") (pinfunction "PB23/EIC/SCOM5PAD3_38") (pintype "bidirectional"))
      (node (ref "R306") (pin "1") (pinfunction "1_1") (pintype "passive"))
    )
    (net (code "85") (name "SAMD21_RESET") (class "Default")
      (node (ref "EDBG") (pin "B4") (pinfunction "PA29_B4") (pintype "bidirectional"))
      (node (ref "IC2") (pin "40") (pinfunction "RESETN_40") (pintype "bidirectional"))
      (node (ref "R103") (pin "1") (pinfunction "1_1") (pintype "passive"))
    )
    (net (code "86") (name "SCK") (class "Default")
      (node (ref "IC2") (pin "26") (pinfunction "PA17/I2C/EIC/SCOM1PAD1+/TC2_26") (pintype "bidirectional"))
      (node (ref "J101") (pin "6") (pinfunction "6_6") (pintype "passive"))
      (node (ref "R109") (pin "1") (pinfunction "1_1") (pintype "passive"))
      (node (ref "R313") (pin "2") (pinfunction "2_2") (pintype "passive"))
      (node (ref "TR3") (pin "3") (pinfunction "G_3") (pintype "passive"))
    )
    (net (code "87") (name "SCL") (class "Default")
      (node (ref "EDBG") (pin "F7") (pinfunction "PA26/PB05_F7") (pintype "bidirectional"))
      (node (ref "IC2") (pin "32") (pinfunction "PA23/I2C/EIC/SCOM5PAD1+/TC4_32") (pintype "bidirectional"))
      (node (ref "J101") (pin "10") (pinfunction "10_10") (pintype "passive"))
      (node (ref "R112") (pin "1") (pinfunction "1_1") (pintype "passive"))
    )
    (net (code "88") (name "SDA") (class "Default")
      (node (ref "EDBG") (pin "G7") (pinfunction "PA12/PA25_G7") (pintype "bidirectional"))
      (node (ref "IC2") (pin "31") (pinfunction "PA22/I2C/EIC/SCOM5PAD0+/TC4_31") (pintype "bidirectional"))
      (node (ref "J101") (pin "9") (pinfunction "9_9") (pintype "passive"))
      (node (ref "R111") (pin "1") (pinfunction "1_1") (pintype "passive"))
    )
    (net (code "89") (name "SS") (class "Default")
      (node (ref "IC2") (pin "27") (pinfunction "PA18/EIC/SCOM1PAD2+/TC3_27") (pintype "bidirectional"))
      (node (ref "J101") (pin "3") (pinfunction "3_3") (pintype "passive"))
      (node (ref "R314") (pin "2") (pinfunction "2_2") (pintype "passive"))
    )
    (net (code "90") (name "STATUS_LED_CTRL") (class "Default")
      (node (ref "EDBG") (pin "F1") (pinfunction "PX59/PX19_F1") (pintype "bidirectional"))
      (node (ref "Q300") (pin "5") (pinfunction "G_5") (pintype "passive"))
      (node (ref "R304") (pin "2") (pinfunction "2_2") (pintype "passive"))
    )
    (net (code "91") (name "SW") (class "Default")
      (node (ref "C200") (pin "2") (pinfunction "2_2") (pintype "passive"))
      (node (ref "D202") (pin "P$1") (pinfunction "K_P$1") (pintype "bidirectional"))
      (node (ref "L201") (pin "P$1") (pinfunction "1_P$1") (pintype "passive"))
      (node (ref "U200") (pin "6") (pinfunction "SW_6") (pintype "output"))
    )
    (net (code "92") (name "SWCLK") (class "Default")
      (node (ref "EDBG") (pin "D6") (pinfunction "PB07_D6") (pintype "bidirectional"))
      (node (ref "J100") (pin "4") (pinfunction "4_4") (pintype "passive"))
      (node (ref "R104") (pin "2") (pinfunction "2_2") (pintype "passive"))
    )
    (net (code "93") (name "SWDIO") (class "Default")
      (node (ref "EDBG") (pin "C5") (pinfunction "PB09_C5") (pintype "bidirectional"))
      (node (ref "J100") (pin "2") (pinfunction "2_2") (pintype "passive"))
      (node (ref "R105") (pin "1") (pinfunction "1_1") (pintype "passive"))
    )
    (net (code "94") (name "TARGET_RESET") (class "Default")
      (node (ref "C101") (pin "1") (pinfunction "1_1") (pintype "passive"))
      (node (ref "ICSP") (pin "5") (pinfunction "5_5") (pintype "passive"))
      (node (ref "J100") (pin "10") (pinfunction "10_10") (pintype "passive"))
      (node (ref "J105") (pin "3") (pinfunction "3_3") (pintype "passive"))
      (node (ref "R100") (pin "1") (pinfunction "1_1") (pintype "passive"))
      (node (ref "R101") (pin "2") (pinfunction "2_2") (pintype "passive"))
      (node (ref "R102") (pin "2") (pinfunction "2_2") (pintype "passive"))
      (node (ref "R103") (pin "2") (pinfunction "2_2") (pintype "passive"))
    )
    (net (code "95") (name "TARGET_RESET_SENSE") (class "Default")
      (node (ref "EDBG") (pin "H2") (pinfunction "PX21_H2") (pintype "bidirectional"))
      (node (ref "R101") (pin "1") (pinfunction "1_1") (pintype "passive"))
    )
    (net (code "96") (name "TARGET_USB_N") (class "Default")
      (node (ref "D103") (pin "3") (pinfunction "3_3") (pintype "bidirectional"))
      (node (ref "IC2") (pin "33") (pinfunction "PA24/EIC/SCOM3PAD2+/TC5_33") (pintype "bidirectional"))
      (node (ref "J107") (pin "D-") (pinfunction "D-_D-") (pintype "bidirectional"))
    )
    (net (code "97") (name "TARGET_USB_P") (class "Default")
      (node (ref "D103") (pin "2") (pinfunction "2_2") (pintype "bidirectional"))
      (node (ref "IC2") (pin "34") (pinfunction "PA25/EIC/SCOM3PAD3+/TC5_34") (pintype "bidirectional"))
      (node (ref "J107") (pin "D+") (pinfunction "D+_D+") (pintype "bidirectional"))
    )
    (net (code "98") (name "TXD") (class "Default")
      (node (ref "IC2") (pin "37") (pinfunction "PB22/EIC/SCOM5PAD2_37") (pintype "bidirectional"))
      (node (ref "R305") (pin "1") (pinfunction "1_1") (pintype "passive"))
    )
    (net (code "99") (name "USB_HOST_ENABLE") (class "Default")
      (node (ref "J107") (pin "ID") (pinfunction "ID_ID") (pintype "bidirectional"))
      (node (ref "Q203") (pin "1") (pinfunction "G_1") (pintype "passive"))
      (node (ref "R113") (pin "1") (pinfunction "1_1") (pintype "passive"))
      (node (ref "R210") (pin "2") (pinfunction "2_2") (pintype "passive"))
    )
    (net (code "100") (name "VCC_EDBG_3V3") (class "Default")
      (node (ref "C309") (pin "1") (pinfunction "1_1") (pintype "passive"))
      (node (ref "C310") (pin "1") (pinfunction "1_1") (pintype "passive"))
      (node (ref "C311") (pin "1") (pinfunction "1_1") (pintype "passive"))
      (node (ref "C312") (pin "1") (pinfunction "1_1") (pintype "passive"))
      (node (ref "C313") (pin "1") (pinfunction "1_1") (pintype "passive"))
      (node (ref "C314") (pin "1") (pinfunction "1_1") (pintype "passive"))
      (node (ref "C315") (pin "1") (pinfunction "1_1") (pintype "passive"))
      (node (ref "EDBG") (pin "B5") (pinfunction "VDDIO_B5") (pintype "bidirectional"))
      (node (ref "EDBG") (pin "B6") (pinfunction "VDDIO1_B6") (pintype "bidirectional"))
      (node (ref "EDBG") (pin "D10") (pinfunction "VDDIN1_D10") (pintype "bidirectional"))
      (node (ref "EDBG") (pin "D9") (pinfunction "VDDIN_D9") (pintype "bidirectional"))
      (node (ref "EDBG") (pin "E5") (pinfunction "VDDIO2_E5") (pintype "bidirectional"))
      (node (ref "EDBG") (pin "F2") (pinfunction "VDDIO3_F2") (pintype "bidirectional"))
      (node (ref "EDBG") (pin "F6") (pinfunction "VDDIO4_F6") (pintype "bidirectional"))
      (node (ref "EDBG") (pin "J5") (pinfunction "VDDIO5_J5") (pintype "bidirectional"))
      (node (ref "J301") (pin "4") (pinfunction "4_4") (pintype "passive"))
      (node (ref "L301") (pin "1") (pinfunction "1_1") (pintype "passive"))
      (node (ref "R300") (pin "2") (pinfunction "2_2") (pintype "passive"))
      (node (ref "R301") (pin "2") (pinfunction "2_2") (pintype "passive"))
      (node (ref "R302") (pin "2") (pinfunction "2_2") (pintype "passive"))
      (node (ref "R319") (pin "2") (pinfunction "2_2") (pintype "passive"))
    )
    (net (code "101") (name "VCC_EDBG_USB") (class "Default")
      (node (ref "EDBG") (pin "A10") (pinfunction "USB_VBUS_A10") (pintype "bidirectional"))
      (node (ref "F300") (pin "2") (pinfunction "2_2") (pintype "passive"))
      (node (ref "Q200") (pin "3") (pinfunction "D_3") (pintype "passive"))
      (node (ref "Q201") (pin "1") (pinfunction "D_1") (pintype "passive"))
      (node (ref "R208") (pin "2") (pinfunction "2_2") (pintype "passive"))
    )
    (net (code "102") (name "VCC_EXT_VIN") (class "Default")
      (node (ref "C203") (pin "+") (pinfunction "+_+") (pintype "passive"))
      (node (ref "J105") (pin "8") (pinfunction "8_8") (pintype "passive"))
      (node (ref "L200") (pin "2") (pinfunction "2_2") (pintype "passive"))
      (node (ref "R200") (pin "1") (pinfunction "1_1") (pintype "passive"))
      (node (ref "U200") (pin "5") (pinfunction "VIN_5") (pintype "input"))
    )
    (net (code "103") (name "VDDCORE") (class "Default")
      (node (ref "C102") (pin "1") (pinfunction "1_1") (pintype "passive"))
      (node (ref "IC2") (pin "43") (pinfunction "VDDCORE1_43") (pintype "input"))
    )
    (net (code "104") (name "VEXT") (class "Default")
      (node (ref "D201") (pin "A") (pinfunction "A_A") (pintype "passive"))
      (node (ref "J200") (pin "2") (pinfunction "2_2") (pintype "power_in"))
      (node (ref "R205") (pin "2") (pinfunction "2_2") (pintype "passive"))
    )
    (net (code "105") (name "VIN_DETECT") (class "Default")
      (node (ref "Q200") (pin "1") (pinfunction "G_1") (pintype "passive"))
      (node (ref "R205") (pin "1") (pinfunction "1_1") (pintype "passive"))
      (node (ref "R206") (pin "2") (pinfunction "2_2") (pintype "passive"))
    )
    (net (code "106") (name "XVCC") (class "Default")
      (node (ref "C307") (pin "1") (pinfunction "1_1") (pintype "passive"))
      (node (ref "D302") (pin "4") (pinfunction "4_4") (pintype "bidirectional"))
      (node (ref "J300") (pin "VBUS") (pinfunction "VUSB_VBUS") (pintype "bidirectional"))
      (node (ref "L300") (pin "1") (pinfunction "1_1") (pintype "passive"))
    )
    (net (code "107") (name "unconnected-(EDBG-PA00{slash}PA18-PadG8)") (class "Default")
      (node (ref "EDBG") (pin "G8") (pinfunction "PA00/PA18_G8") (pintype "bidirectional"))
    )
    (net (code "108") (name "unconnected-(EDBG-PA01{slash}PA17-PadG10)") (class "Default")
      (node (ref "EDBG") (pin "G10") (pinfunction "PA01/PA17_G10") (pintype "bidirectional"))
    )
    (net (code "109") (name "unconnected-(EDBG-PA02{slash}PX47-PadE1)") (class "Default")
      (node (ref "EDBG") (pin "E1") (pinfunction "PA02/PX47_E1") (pintype "bidirectional"))
    )
    (net (code "110") (name "unconnected-(EDBG-PA05-PadG9)") (class "Default")
      (node (ref "EDBG") (pin "G9") (pinfunction "PA05_G9") (pintype "bidirectional"))
    )
    (net (code "111") (name "unconnected-(EDBG-PA06{slash}PA13-PadE8)") (class "Default")
      (node (ref "EDBG") (pin "E8") (pinfunction "PA06/PA13_E8") (pintype "bidirectional"))
    )
    (net (code "112") (name "unconnected-(EDBG-PA07{slash}PA19-PadH10)") (class "Default")
      (node (ref "EDBG") (pin "H10") (pinfunction "PA07/PA19_H10") (pintype "bidirectional"))
    )
    (net (code "113") (name "unconnected-(EDBG-PA14{slash}PX11-PadK7)") (class "Default")
      (node (ref "EDBG") (pin "K7") (pinfunction "PA14/PX11_K7") (pintype "bidirectional"))
    )
    (net (code "114") (name "unconnected-(EDBG-PA15{slash}PX45-PadJ7)") (class "Default")
      (node (ref "EDBG") (pin "J7") (pinfunction "PA15/PX45_J7") (pintype "bidirectional"))
    )
    (net (code "115") (name "unconnected-(EDBG-PA16-PadE7)") (class "Default")
      (node (ref "EDBG") (pin "E7") (pinfunction "PA16_E7") (pintype "bidirectional"))
    )
    (net (code "116") (name "unconnected-(EDBG-PA22{slash}PX20-PadH6)") (class "Default")
      (node (ref "EDBG") (pin "H6") (pinfunction "PA22/PX20_H6") (pintype "bidirectional"))
    )
    (net (code "117") (name "unconnected-(EDBG-PA23{slash}PX46-PadG6)") (class "Default")
      (node (ref "EDBG") (pin "G6") (pinfunction "PA23/PX46_G6") (pintype "bidirectional"))
    )
    (net (code "118") (name "unconnected-(EDBG-PA24{slash}PX17-PadJ10)") (class "Default")
      (node (ref "EDBG") (pin "J10") (pinfunction "PA24/PX17_J10") (pintype "bidirectional"))
    )
    (net (code "119") (name "unconnected-(EDBG-PA27-PadA2)") (class "Default")
      (node (ref "EDBG") (pin "A2") (pinfunction "PA27_A2") (pintype "bidirectional"))
    )
    (net (code "120") (name "unconnected-(EDBG-PA28-PadA1)") (class "Default")
      (node (ref "EDBG") (pin "A1") (pinfunction "PA28_A1") (pintype "bidirectional"))
    )
    (net (code "121") (name "unconnected-(EDBG-PA30-PadA4)") (class "Default")
      (node (ref "EDBG") (pin "A4") (pinfunction "PA30_A4") (pintype "bidirectional"))
    )
    (net (code "122") (name "unconnected-(EDBG-PA31-PadC2)") (class "Default")
      (node (ref "EDBG") (pin "C2") (pinfunction "PA31_C2") (pintype "bidirectional"))
    )
    (net (code "123") (name "unconnected-(EDBG-PB00-PadB1)") (class "Default")
      (node (ref "EDBG") (pin "B1") (pinfunction "PB00_B1") (pintype "bidirectional"))
    )
    (net (code "124") (name "unconnected-(EDBG-PB01-PadB2)") (class "Default")
      (node (ref "EDBG") (pin "B2") (pinfunction "PB01_B2") (pintype "bidirectional"))
    )
    (net (code "125") (name "unconnected-(EDBG-PB02-PadB3)") (class "Default")
      (node (ref "EDBG") (pin "B3") (pinfunction "PB02_B3") (pintype "bidirectional"))
    )
    (net (code "126") (name "unconnected-(EDBG-PB03-PadC4)") (class "Default")
      (node (ref "EDBG") (pin "C4") (pinfunction "PB03_C4") (pintype "bidirectional"))
    )
    (net (code "127") (name "unconnected-(EDBG-PB04-PadA3)") (class "Default")
      (node (ref "EDBG") (pin "A3") (pinfunction "PB04_A3") (pintype "bidirectional"))
    )
    (net (code "128") (name "unconnected-(EDBG-PB06-PadD7)") (class "Default")
      (node (ref "EDBG") (pin "D7") (pinfunction "PB06_D7") (pintype "bidirectional"))
    )
    (net (code "129") (name "unconnected-(EDBG-PB08-PadC6)") (class "Default")
      (node (ref "EDBG") (pin "C6") (pinfunction "PB08_C6") (pintype "bidirectional"))
    )
    (net (code "130") (name "unconnected-(EDBG-PB10-PadD5)") (class "Default")
      (node (ref "EDBG") (pin "D5") (pinfunction "PB10_D5") (pintype "bidirectional"))
    )
    (net (code "131") (name "unconnected-(EDBG-PB11-PadC1)") (class "Default")
      (node (ref "EDBG") (pin "C1") (pinfunction "PB11_C1") (pintype "bidirectional"))
    )
    (net (code "132") (name "unconnected-(EDBG-PC00{slash}PX14-PadK5)") (class "Default")
      (node (ref "EDBG") (pin "K5") (pinfunction "PC00/PX14_K5") (pintype "bidirectional"))
    )
    (net (code "133") (name "unconnected-(EDBG-PC01-PadK6)") (class "Default")
      (node (ref "EDBG") (pin "K6") (pinfunction "PC01_K6") (pintype "bidirectional"))
    )
    (net (code "134") (name "unconnected-(EDBG-PC04-PadB7)") (class "Default")
      (node (ref "EDBG") (pin "B7") (pinfunction "PC04_B7") (pintype "bidirectional"))
    )
    (net (code "135") (name "unconnected-(EDBG-PC05-PadA7)") (class "Default")
      (node (ref "EDBG") (pin "A7") (pinfunction "PC05_A7") (pintype "bidirectional"))
    )
    (net (code "136") (name "unconnected-(EDBG-PX00-PadG4)") (class "Default")
      (node (ref "EDBG") (pin "G4") (pinfunction "PX00_G4") (pintype "bidirectional"))
    )
    (net (code "137") (name "unconnected-(EDBG-PX01-PadG2)") (class "Default")
      (node (ref "EDBG") (pin "G2") (pinfunction "PX01_G2") (pintype "bidirectional"))
    )
    (net (code "138") (name "unconnected-(EDBG-PX02-PadG3)") (class "Default")
      (node (ref "EDBG") (pin "G3") (pinfunction "PX02_G3") (pintype "bidirectional"))
    )
    (net (code "139") (name "unconnected-(EDBG-PX03-PadJ1)") (class "Default")
      (node (ref "EDBG") (pin "J1") (pinfunction "PX03_J1") (pintype "bidirectional"))
    )
    (net (code "140") (name "unconnected-(EDBG-PX04-PadH1)") (class "Default")
      (node (ref "EDBG") (pin "H1") (pinfunction "PX04_H1") (pintype "bidirectional"))
    )
    (net (code "141") (name "unconnected-(EDBG-PX05-PadG1)") (class "Default")
      (node (ref "EDBG") (pin "G1") (pinfunction "PX05_G1") (pintype "bidirectional"))
    )
    (net (code "142") (name "unconnected-(EDBG-PX06-PadF3)") (class "Default")
      (node (ref "EDBG") (pin "F3") (pinfunction "PX06_F3") (pintype "bidirectional"))
    )
    (net (code "143") (name "unconnected-(EDBG-PX07-PadF4)") (class "Default")
      (node (ref "EDBG") (pin "F4") (pinfunction "PX07_F4") (pintype "bidirectional"))
    )
    (net (code "144") (name "unconnected-(EDBG-PX08-PadE3)") (class "Default")
      (node (ref "EDBG") (pin "E3") (pinfunction "PX08_E3") (pintype "bidirectional"))
    )
    (net (code "145") (name "unconnected-(EDBG-PX09-PadE4)") (class "Default")
      (node (ref "EDBG") (pin "E4") (pinfunction "PX09_E4") (pintype "bidirectional"))
    )
    (net (code "146") (name "unconnected-(EDBG-PX10-PadD2)") (class "Default")
      (node (ref "EDBG") (pin "D2") (pinfunction "PX10_D2") (pintype "bidirectional"))
    )
    (net (code "147") (name "unconnected-(EDBG-PX12-PadD1)") (class "Default")
      (node (ref "EDBG") (pin "D1") (pinfunction "PX12_D1") (pintype "bidirectional"))
    )
    (net (code "148") (name "unconnected-(EDBG-PX13-PadD3)") (class "Default")
      (node (ref "EDBG") (pin "D3") (pinfunction "PX13_D3") (pintype "bidirectional"))
    )
    (net (code "149") (name "unconnected-(EDBG-PX23-PadK1)") (class "Default")
      (node (ref "EDBG") (pin "K1") (pinfunction "PX23_K1") (pintype "bidirectional"))
    )
    (net (code "150") (name "unconnected-(EDBG-PX24-PadJ2)") (class "Default")
      (node (ref "EDBG") (pin "J2") (pinfunction "PX24_J2") (pintype "bidirectional"))
    )
    (net (code "151") (name "unconnected-(EDBG-PX25-PadH4)") (class "Default")
      (node (ref "EDBG") (pin "H4") (pinfunction "PX25_H4") (pintype "bidirectional"))
    )
    (net (code "152") (name "unconnected-(EDBG-PX26-PadJ3)") (class "Default")
      (node (ref "EDBG") (pin "J3") (pinfunction "PX26_J3") (pintype "bidirectional"))
    )
    (net (code "153") (name "unconnected-(EDBG-PX31-PadH5)") (class "Default")
      (node (ref "EDBG") (pin "H5") (pinfunction "PX31_H5") (pintype "bidirectional"))
    )
    (net (code "154") (name "unconnected-(EDBG-PX53{slash}PX16-PadD4)") (class "Default")
      (node (ref "EDBG") (pin "D4") (pinfunction "PX53/PX16_D4") (pintype "bidirectional"))
    )
    (net (code "155") (name "unconnected-(J100-Pad6)") (class "Default")
      (node (ref "J100") (pin "6") (pinfunction "6_6") (pintype "passive"))
    )
    (net (code "156") (name "unconnected-(J100-Pad7)") (class "Default")
      (node (ref "J100") (pin "7") (pinfunction "7_7") (pintype "passive"))
    )
    (net (code "157") (name "unconnected-(J100-Pad8)") (class "Default")
      (node (ref "J100") (pin "8") (pinfunction "8_8") (pintype "passive"))
    )
    (net (code "158") (name "unconnected-(J300-PadID)") (class "Default")
      (node (ref "J300") (pin "ID") (pinfunction "ID_ID") (pintype "bidirectional"))
    )
    (net (code "159") (name "unconnected-(J301-Pad7)") (class "Default")
      (node (ref "J301") (pin "7") (pinfunction "7_7") (pintype "passive"))
    )
    (net (code "160") (name "unconnected-(J301-Pad8)") (class "Default")
      (node (ref "J301") (pin "8") (pinfunction "8_8") (pintype "passive"))
    )
    (net (code "161") (name "unconnected-(X300-GND-Pad2)") (class "Default")
      (node (ref "X300") (pin "2") (pinfunction "GND_2") (pintype "passive"))
    )
    (net (code "162") (name "unconnected-(X300-GND-Pad4)") (class "Default")
      (node (ref "X300") (pin "4") (pinfunction "GND_4") (pintype "passive"))
    )
  )
)
